# e_book_reader.net
KiCad netlist of a schematic drawn in EAGLE
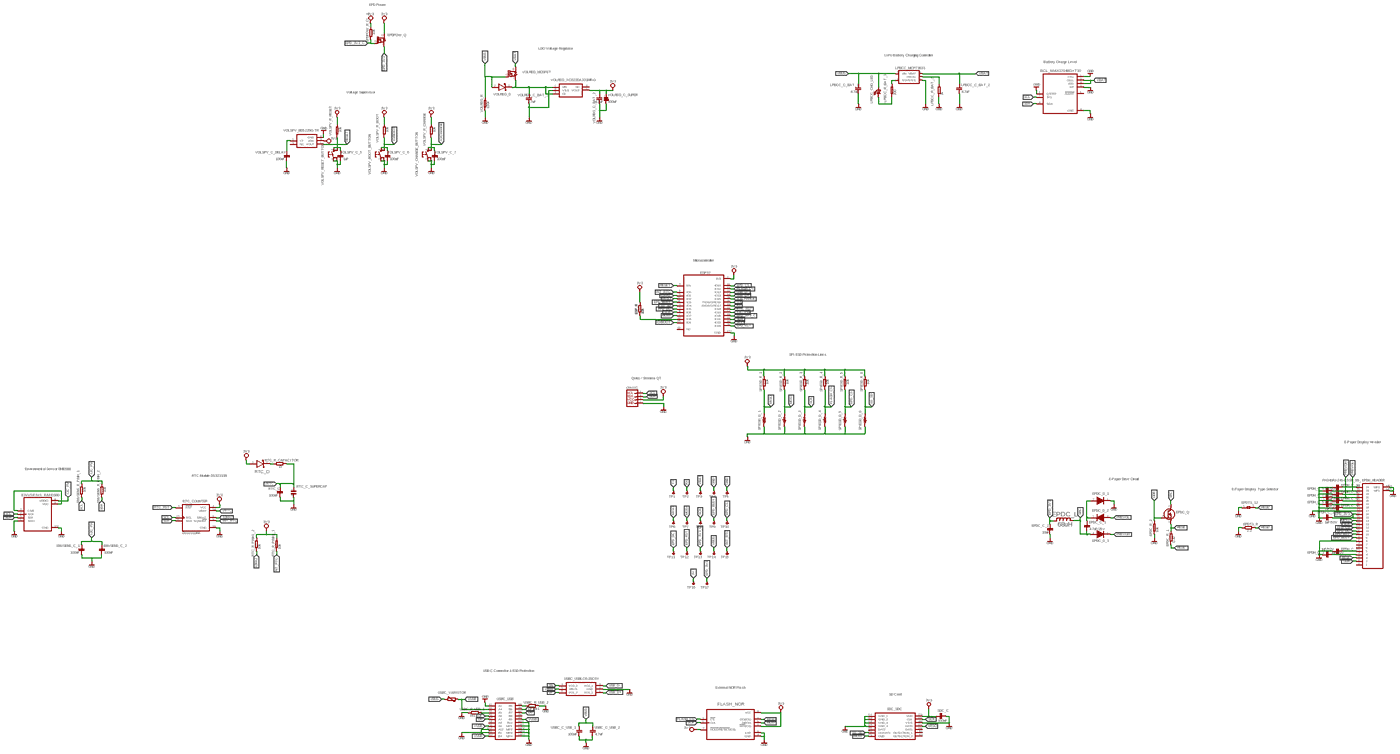
[diagram p0: schematic, sheet 1, overview]
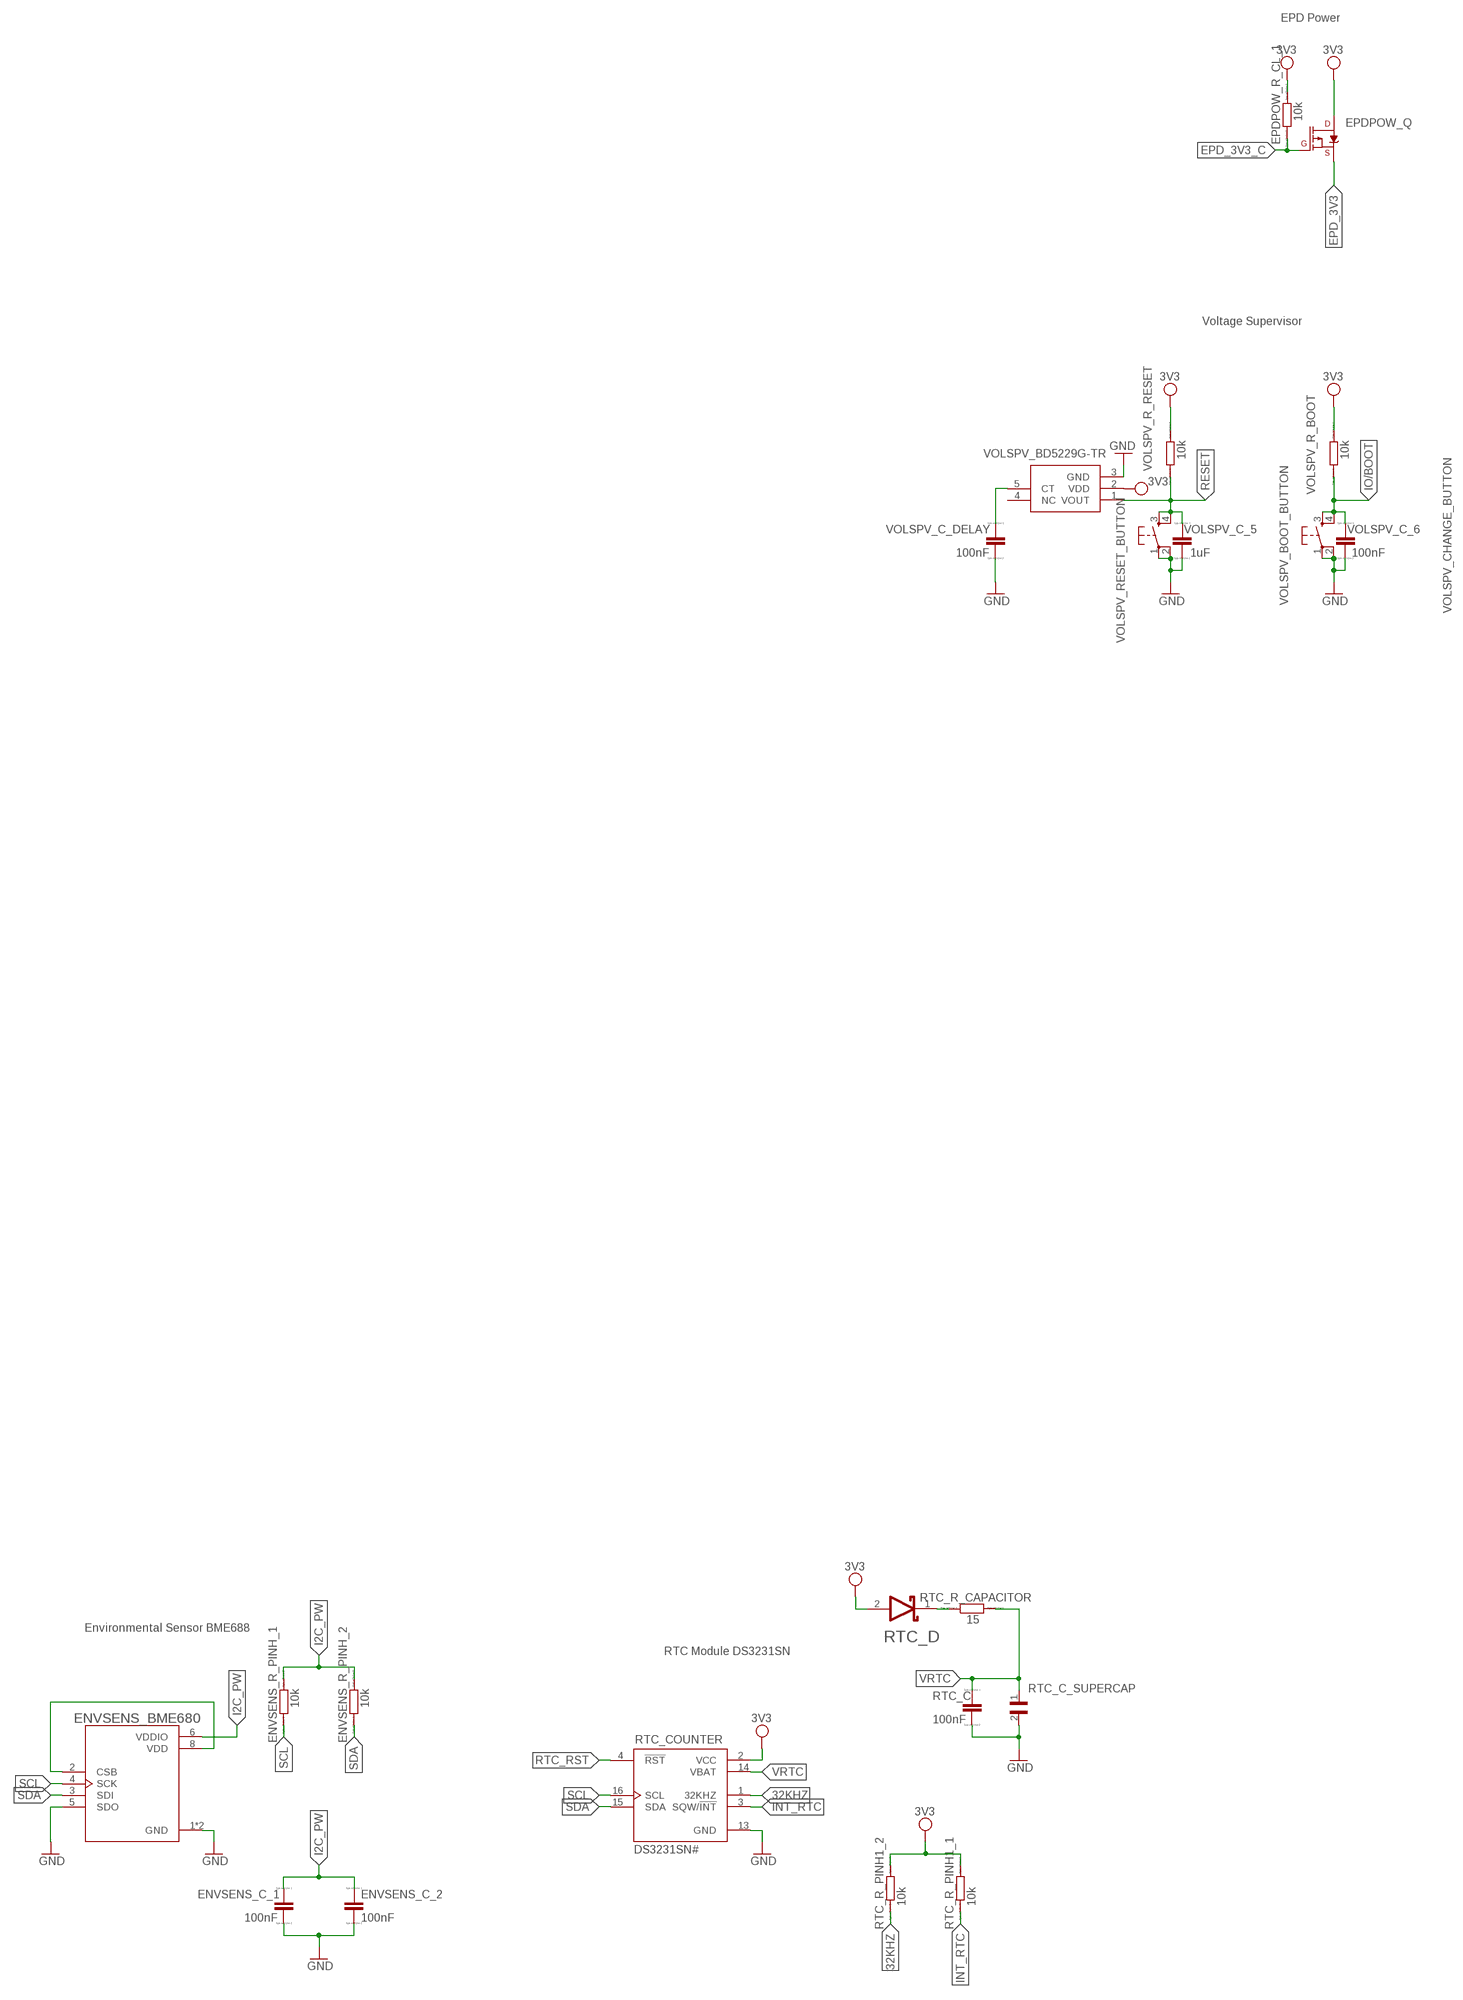
[diagram p1: schematic, sheet 1, part 1 of 5]
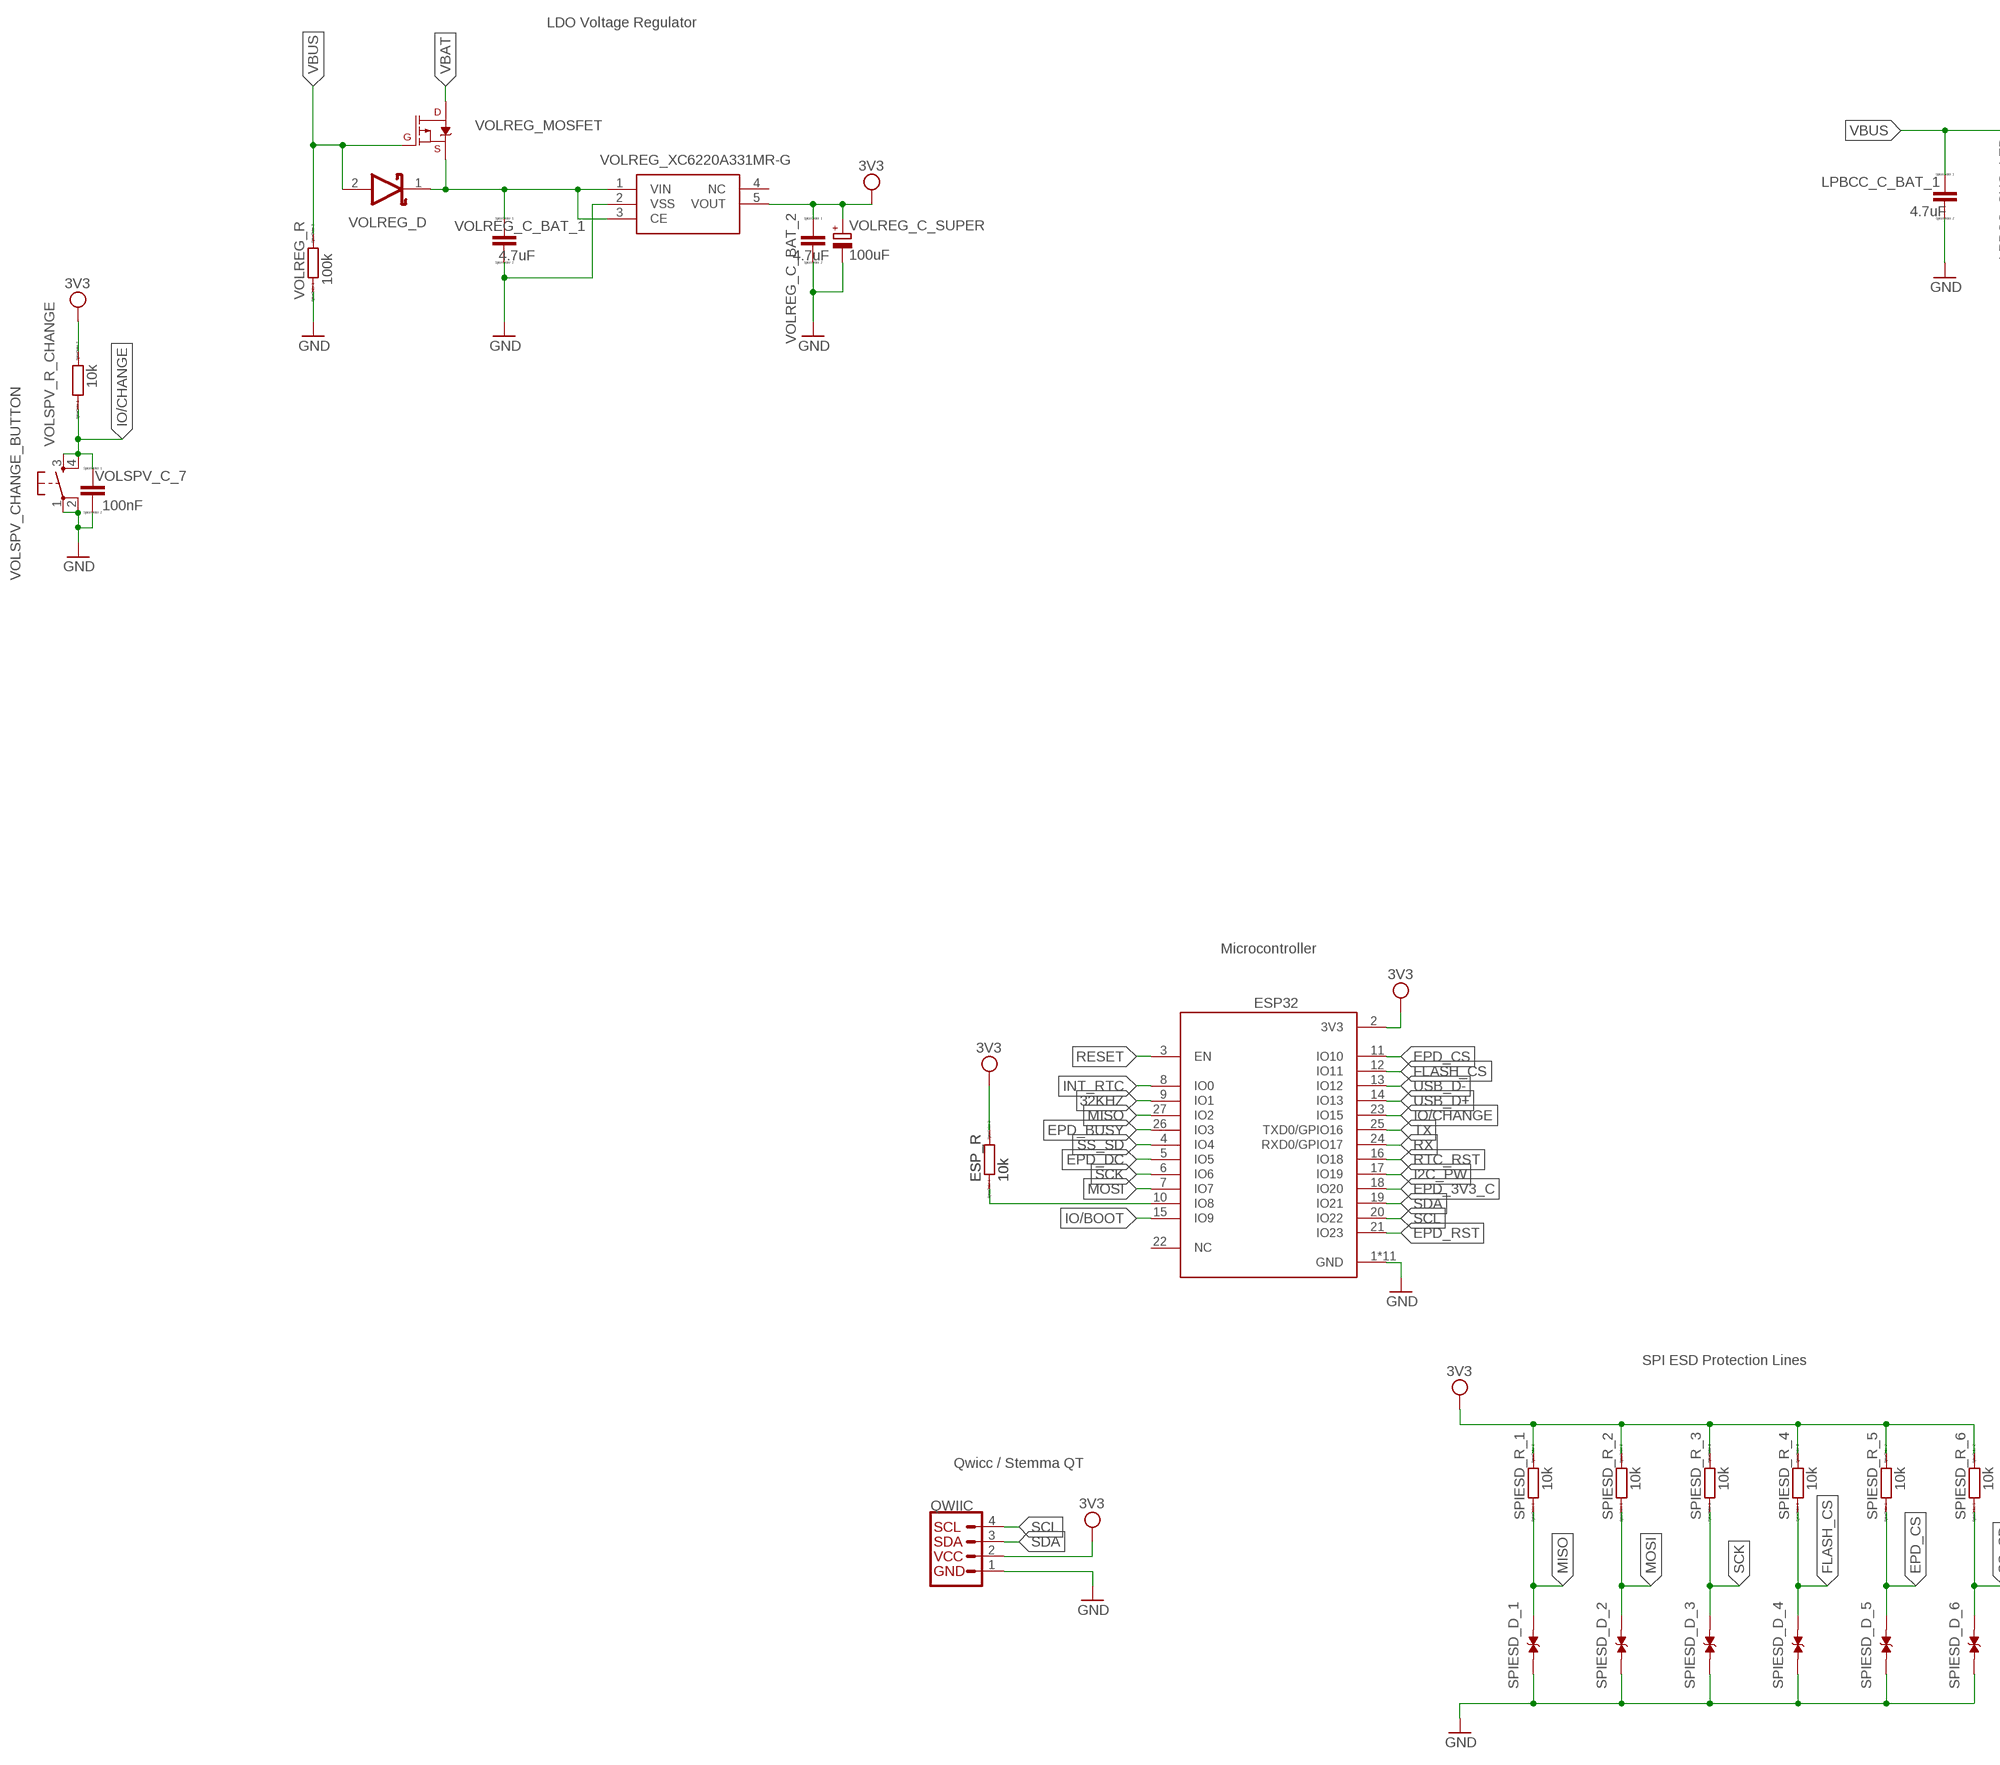
[diagram p2: schematic, sheet 1, part 2 of 5]
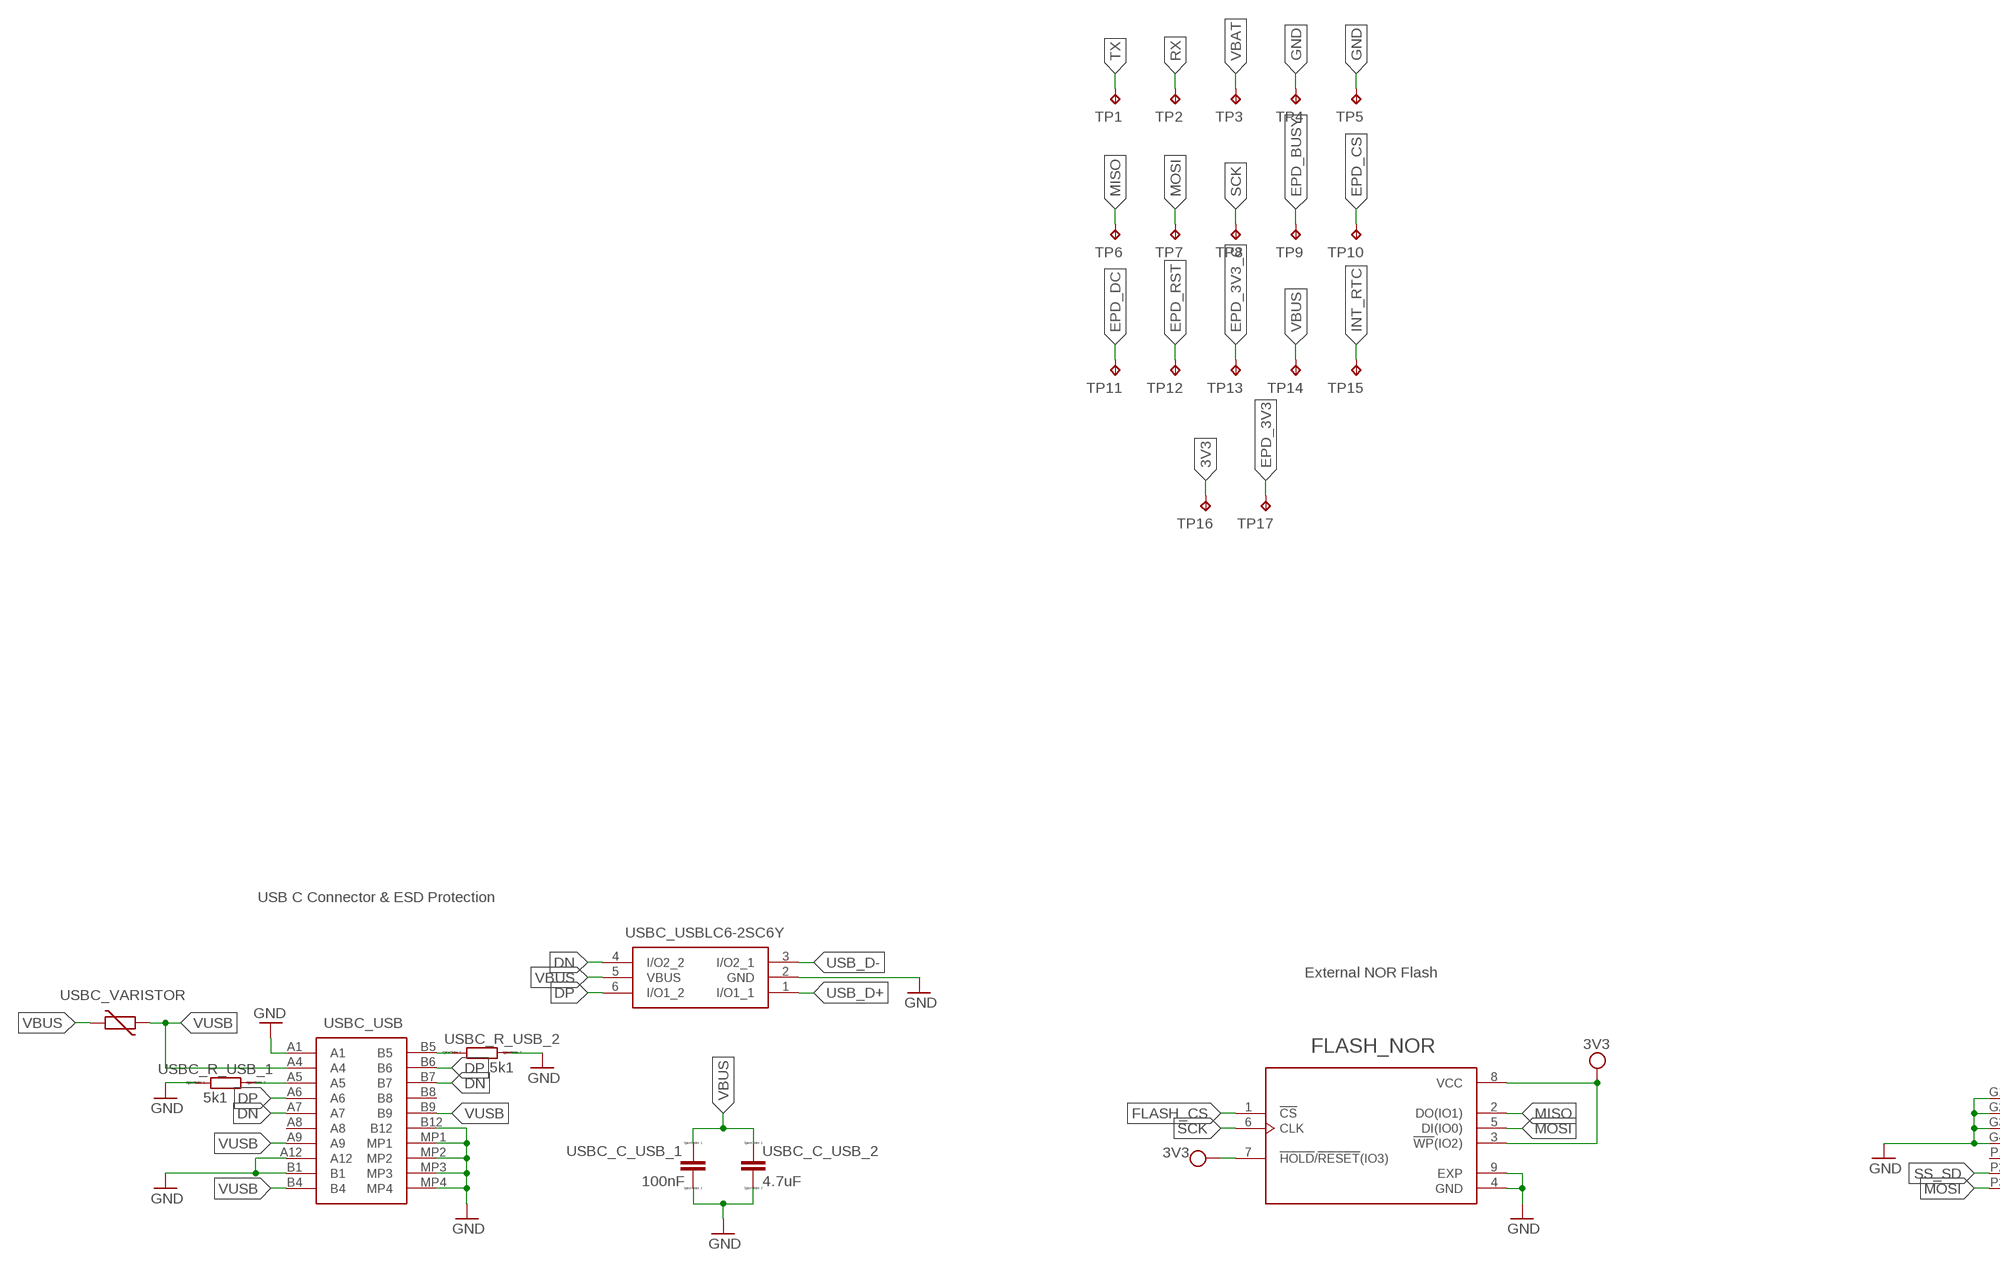
[diagram p3: schematic, sheet 1, part 3 of 5]
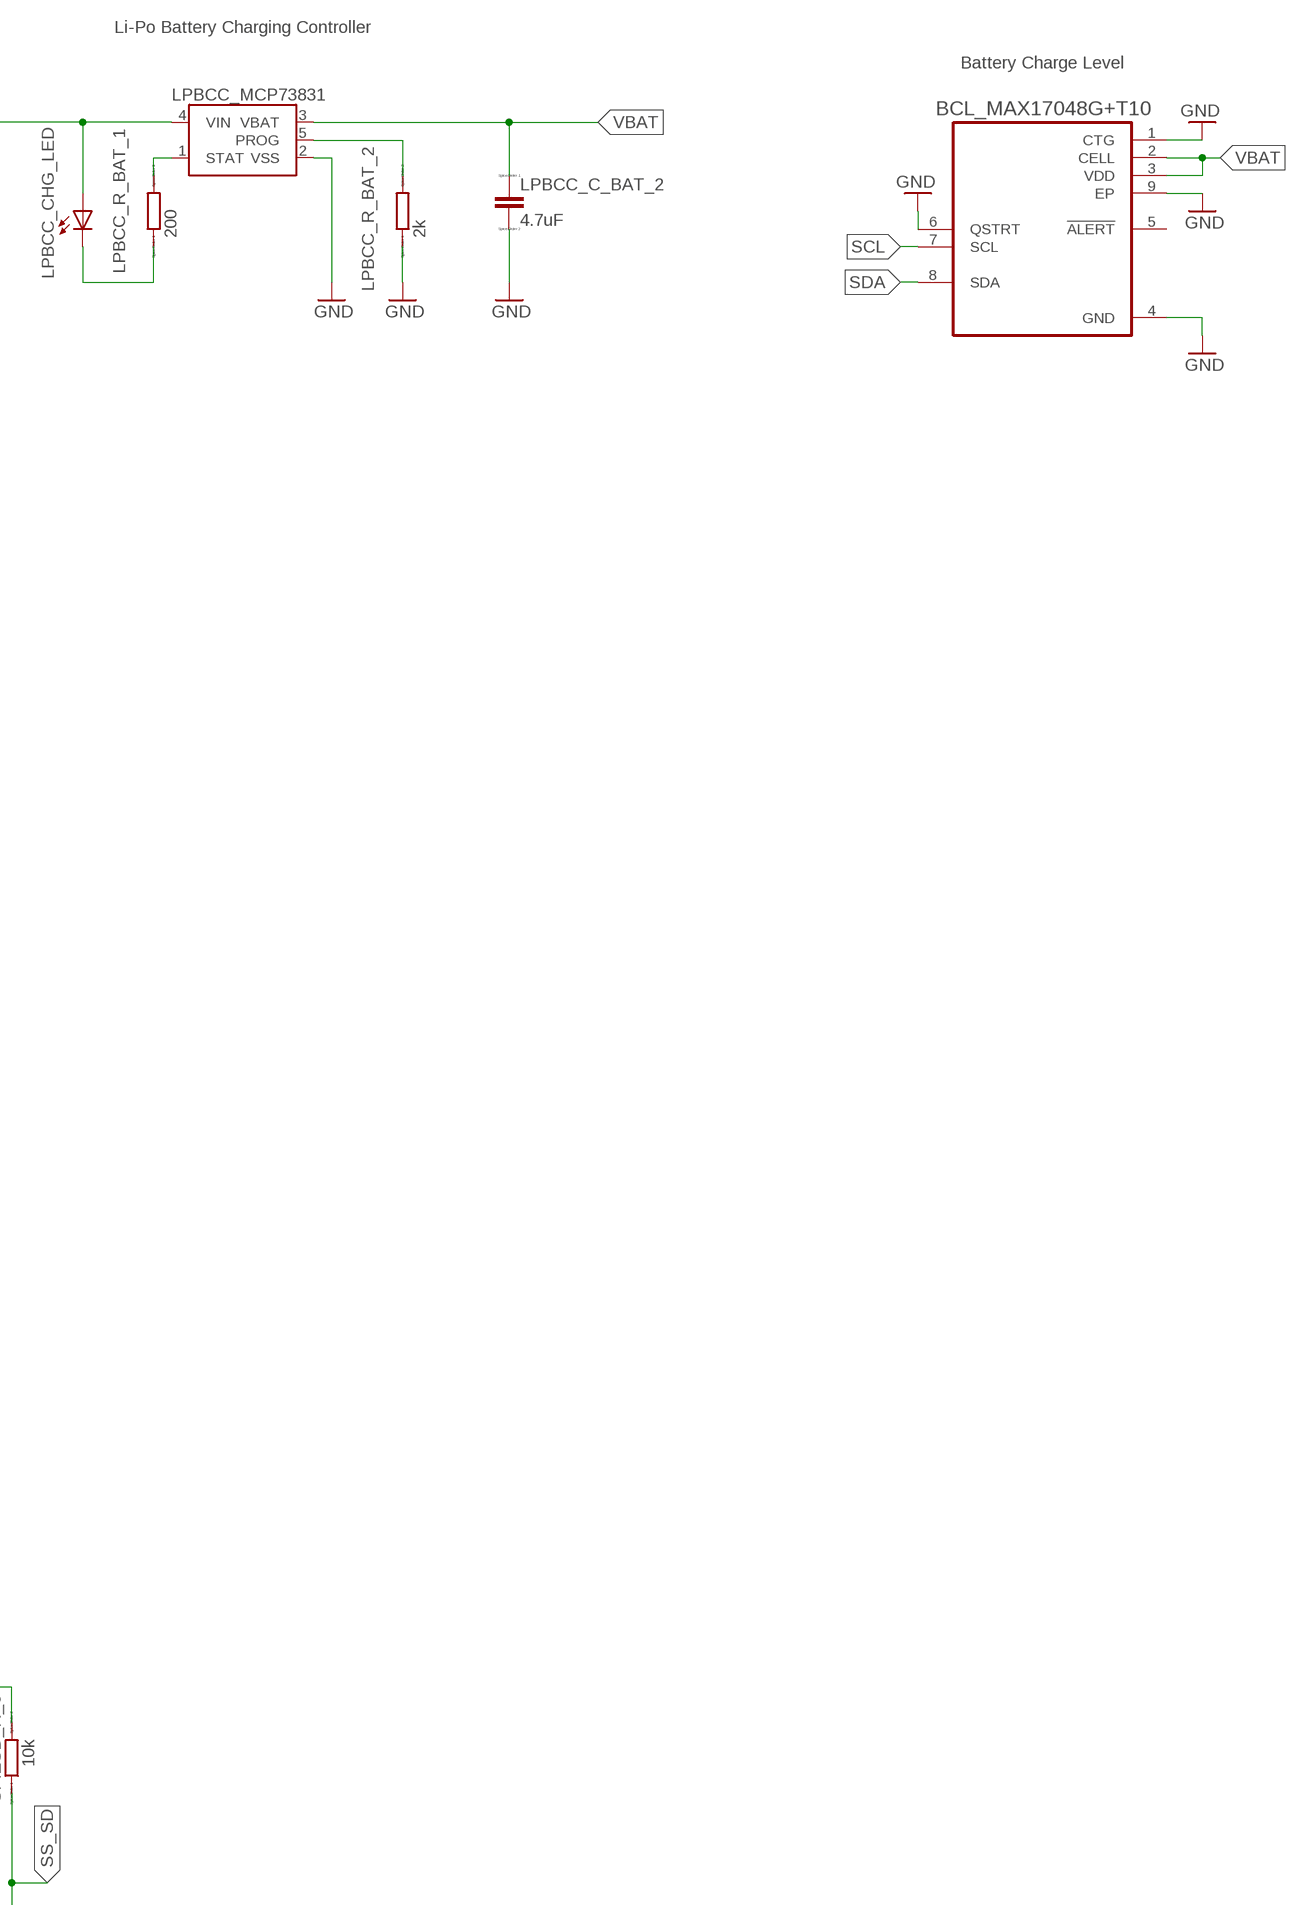
[diagram p4: schematic, sheet 1, part 4 of 5]
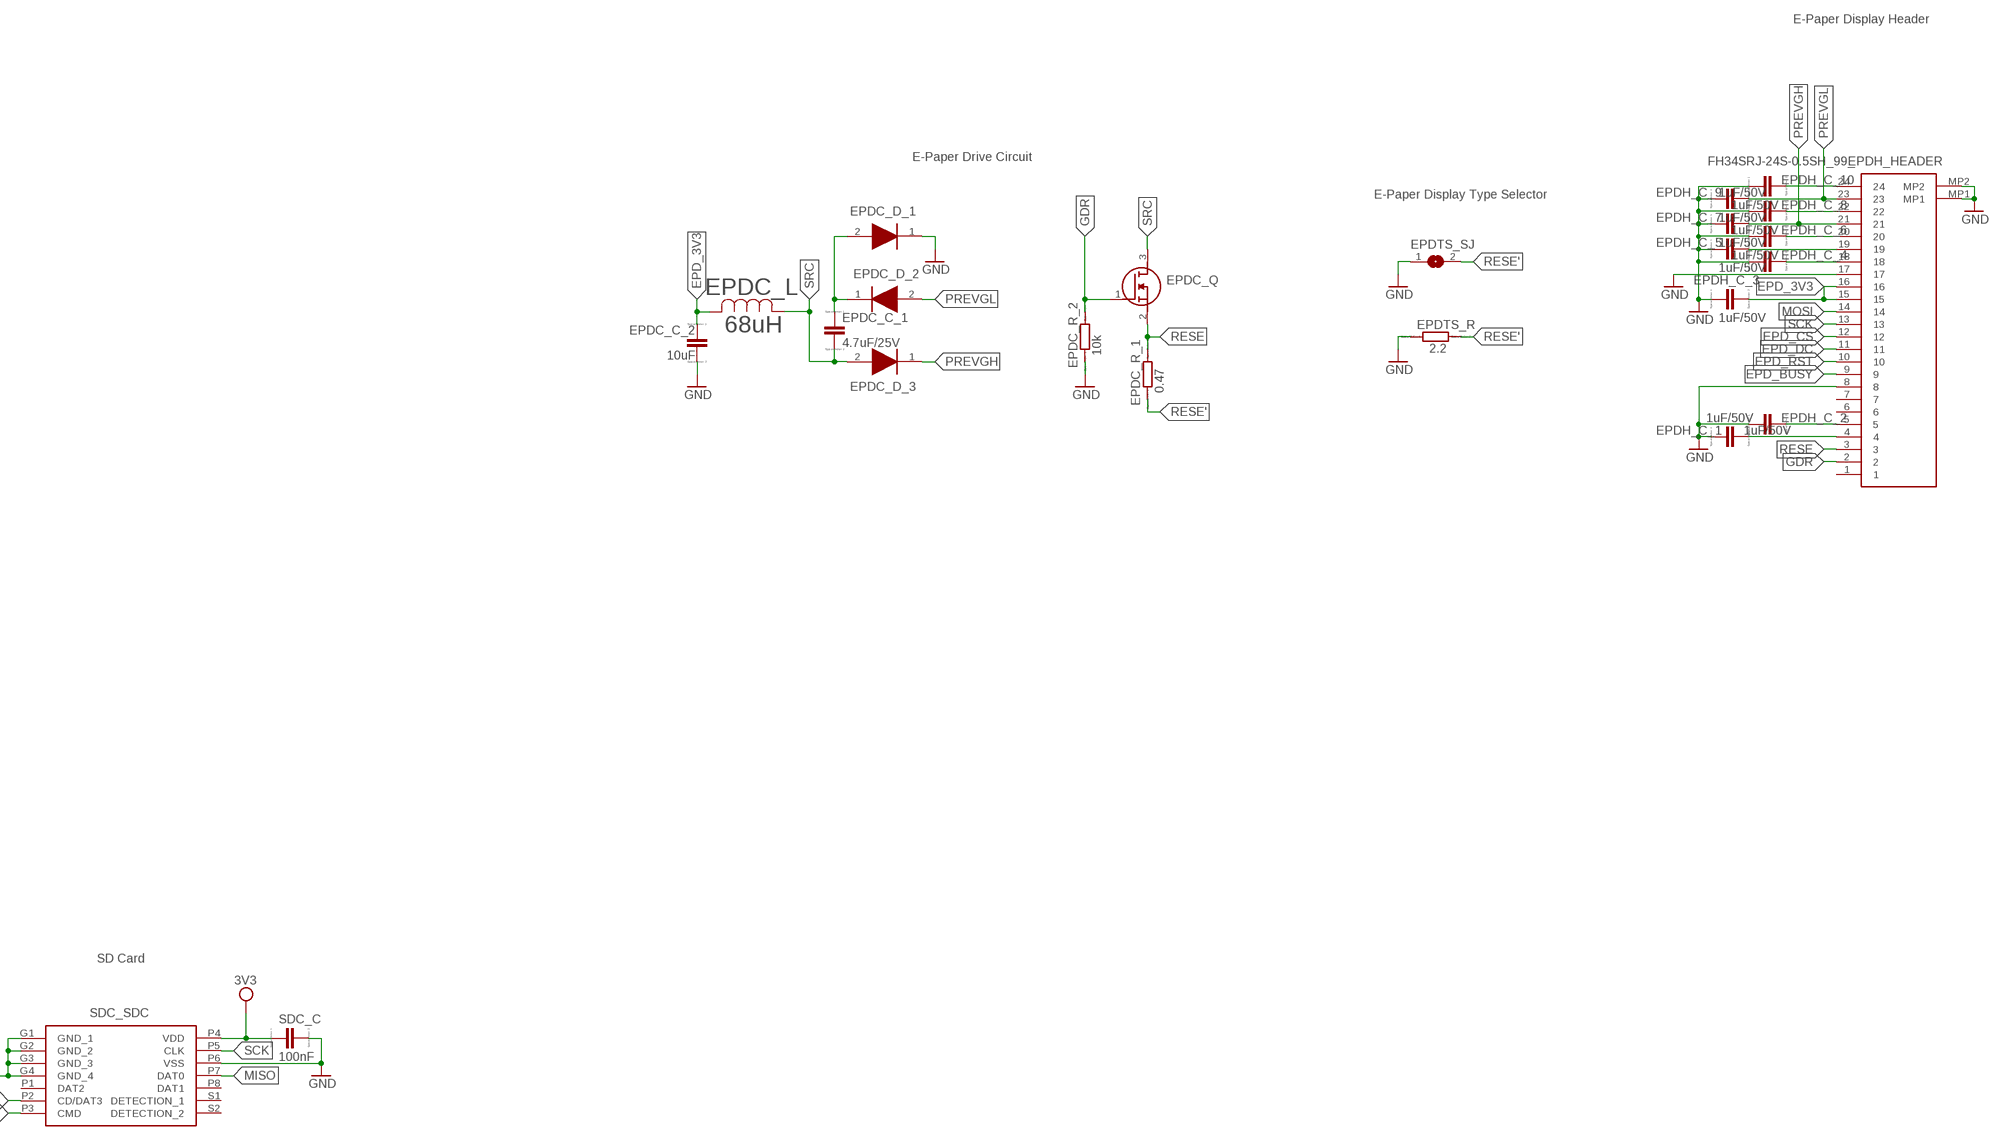
[diagram p5: schematic, sheet 1, part 5 of 5]

(export (version "E")
  (design (tool "Eeschema 10.0.6"))
  (components
    (comp (ref "BCL_MAX17048G+T10")
      (value "MAX17048G+T10")
      (footprint "eagle-import:SON50P200X200X80-9N")
      (libsource (lib "eagle-import") (part "MAX17048G+T10"))
    )
    (comp (ref "ENVSENS_BME680")
      (value "ESP32_WROVER_BME680_BME680")
      (footprint "eagle-import:ESP32_WROVER_BME680_PSON80P300X300X100-8N")
      (libsource (lib "eagle-import") (part "ESP32_WROVER_BME680_BME680"))
    )
    (comp (ref "ENVSENS_C_1")
      (value "100nF")
      (footprint "eagle-import:EAGLE-LTSPICE_C0402")
      (libsource (lib "eagle-import") (part "EAGLE-LTSPICE_CC0402"))
    )
    (comp (ref "ENVSENS_C_2")
      (value "100nF")
      (footprint "eagle-import:EAGLE-LTSPICE_C0402")
      (libsource (lib "eagle-import") (part "EAGLE-LTSPICE_CC0402"))
    )
    (comp (ref "ENVSENS_R_PINH_1")
      (value "10k")
      (footprint "eagle-import:ESP32_WROVER_EAGLE-LTSPICE_R0402")
      (libsource (lib "eagle-import") (part "ESP32_WROVER_EAGLE-LTSPICE_RR0402"))
    )
    (comp (ref "ENVSENS_R_PINH_2")
      (value "10k")
      (footprint "eagle-import:ESP32_WROVER_EAGLE-LTSPICE_R0402")
      (libsource (lib "eagle-import") (part "ESP32_WROVER_EAGLE-LTSPICE_RR0402"))
    )
    (comp (ref "EPDC_C_1")
      (value "4.7uF/25V")
      (footprint "eagle-import:EAGLE-LTSPICE_C0402")
      (libsource (lib "eagle-import") (part "EAGLE-LTSPICE_CC0402"))
    )
    (comp (ref "EPDC_C_2")
      (value "10uF")
      (footprint "eagle-import:EAGLE-LTSPICE_C0402")
      (libsource (lib "eagle-import") (part "EAGLE-LTSPICE_CC0402"))
    )
    (comp (ref "EPDC_D_1")
      (value "MBR0530")
      (footprint "eagle-import:SOD3716X135N")
      (libsource (lib "eagle-import") (part "MBR0530"))
    )
    (comp (ref "EPDC_D_2")
      (value "MBR0530")
      (footprint "eagle-import:SOD3716X135N")
      (libsource (lib "eagle-import") (part "MBR0530"))
    )
    (comp (ref "EPDC_D_3")
      (value "MBR0530")
      (footprint "eagle-import:SOD3716X135N")
      (libsource (lib "eagle-import") (part "MBR0530"))
    )
    (comp (ref "EPDC_L")
      (value "68uH")
      (footprint "eagle-import:IND_4828-WE-TPC_WRE")
      (libsource (lib "eagle-import") (part "744043680IND_4828-WE-TPC_WRE"))
    )
    (comp (ref "EPDC_Q")
      (value "SI1308EDL-T1-GE3")
      (footprint "eagle-import:SOT65P210X110-3N")
      (libsource (lib "eagle-import") (part "SI1308EDL-T1-GE3"))
    )
    (comp (ref "EPDC_R_1")
      (value "0.47")
      (footprint "eagle-import:ESP32_WROVER_EAGLE-LTSPICE_R0402")
      (libsource (lib "eagle-import") (part "ESP32_WROVER_EAGLE-LTSPICE_RR0402"))
    )
    (comp (ref "EPDC_R_2")
      (value "10k")
      (footprint "eagle-import:ESP32_WROVER_EAGLE-LTSPICE_R0402")
      (libsource (lib "eagle-import") (part "ESP32_WROVER_EAGLE-LTSPICE_RR0402"))
    )
    (comp (ref "EPDH_C_1")
      (value "1uF/50V")
      (footprint "eagle-import:EAGLE-LTSPICE_C0402")
      (libsource (lib "eagle-import") (part "EAGLE-LTSPICE_CC0402"))
    )
    (comp (ref "EPDH_C_2")
      (value "1uF/50V")
      (footprint "eagle-import:EAGLE-LTSPICE_C0402")
      (libsource (lib "eagle-import") (part "EAGLE-LTSPICE_CC0402"))
    )
    (comp (ref "EPDH_C_3")
      (value "1uF/50V")
      (footprint "eagle-import:EAGLE-LTSPICE_C0402")
      (libsource (lib "eagle-import") (part "EAGLE-LTSPICE_CC0402"))
    )
    (comp (ref "EPDH_C_4")
      (value "1uF/50V")
      (footprint "eagle-import:EAGLE-LTSPICE_C0402")
      (libsource (lib "eagle-import") (part "EAGLE-LTSPICE_CC0402"))
    )
    (comp (ref "EPDH_C_5")
      (value "1uF/50V")
      (footprint "eagle-import:EAGLE-LTSPICE_C0402")
      (libsource (lib "eagle-import") (part "EAGLE-LTSPICE_CC0402"))
    )
    (comp (ref "EPDH_C_6")
      (value "1uF/50V")
      (footprint "eagle-import:EAGLE-LTSPICE_C0402")
      (libsource (lib "eagle-import") (part "EAGLE-LTSPICE_CC0402"))
    )
    (comp (ref "EPDH_C_7")
      (value "1uF/50V")
      (footprint "eagle-import:EAGLE-LTSPICE_C0402")
      (libsource (lib "eagle-import") (part "EAGLE-LTSPICE_CC0402"))
    )
    (comp (ref "EPDH_C_8")
      (value "1uF/50V")
      (footprint "eagle-import:EAGLE-LTSPICE_C0402")
      (libsource (lib "eagle-import") (part "EAGLE-LTSPICE_CC0402"))
    )
    (comp (ref "EPDH_C_9")
      (value "1uF/50V")
      (footprint "eagle-import:EAGLE-LTSPICE_C0402")
      (libsource (lib "eagle-import") (part "EAGLE-LTSPICE_CC0402"))
    )
    (comp (ref "EPDH_C_10")
      (value "1uF/50V")
      (footprint "eagle-import:EAGLE-LTSPICE_C0402")
      (libsource (lib "eagle-import") (part "EAGLE-LTSPICE_CC0402"))
    )
    (comp (ref "EPDH_HEADER")
      (value "FH34SRJ-24S-0.5SH_99_")
      (footprint "eagle-import:FH34SRJ24S05SH99")
      (libsource (lib "eagle-import") (part "FH34SRJ-24S-0.5SH_99_"))
    )
    (comp (ref "EPDPOW_Q")
      (value "20V/4.2A/52mΩ/1.4W")
      (footprint "eagle-import:ESP32_WROVER_SPARKFUN-DISCRETESEMI_SOT23-3")
      (libsource (lib "eagle-import") (part "ESP32_WROVER_SPARKFUN-DISCRETESEMI_MOSFET_PCH-DMG2305UX-7"))
    )
    (comp (ref "EPDPOW_R_CL_1")
      (value "10k")
      (footprint "eagle-import:ESP32_WROVER_EAGLE-LTSPICE_R0402")
      (libsource (lib "eagle-import") (part "ESP32_WROVER_EAGLE-LTSPICE_RR0402"))
    )
    (comp (ref "EPDTS_R")
      (value "2.2")
      (footprint "eagle-import:ESP32_WROVER_EAGLE-LTSPICE_R0402")
      (libsource (lib "eagle-import") (part "ESP32_WROVER_EAGLE-LTSPICE_RR0402"))
    )
    (comp (ref "EPDTS_SJ")
      (value "SJ")
      (footprint "eagle-import:SJ")
      (libsource (lib "eagle-import") (part "SJ"))
    )
    (comp (ref "ESP32")
      (value "ESP32-C6-WROOM-1-N8")
      (footprint "eagle-import:XCVR_ESP32-C6-WROOM-1-N8")
      (fields (field (name "MF") "Espressif Systems"))
      (libsource (lib "eagle-import") (part "ESP32-C6-WROOM-1-N8"))
    )
    (comp (ref "ESP_R")
      (value "10k")
      (footprint "eagle-import:ESP32_WROVER_EAGLE-LTSPICE_R0402")
      (libsource (lib "eagle-import") (part "ESP32_WROVER_EAGLE-LTSPICE_RR0402"))
    )
    (comp (ref "FLASH_NOR")
      (value "W25Q512JVEIQ")
      (footprint "eagle-import:SON127P600X800X80-9N")
      (libsource (lib "eagle-import") (part "W25Q512JVEIQ"))
    )
    (comp (ref "LPBCC_CHG_LED")
      (value "ADAFRUIT_LED")
      (footprint "eagle-import:ADAFRUIT_CHIP-LED0603")
      (libsource (lib "eagle-import") (part "ADAFRUIT_LED"))
    )
    (comp (ref "LPBCC_C_BAT_1")
      (value "4.7uF")
      (footprint "eagle-import:EAGLE-LTSPICE_C0402")
      (libsource (lib "eagle-import") (part "EAGLE-LTSPICE_CC0402"))
    )
    (comp (ref "LPBCC_C_BAT_2")
      (value "4.7uF")
      (footprint "eagle-import:EAGLE-LTSPICE_C0402")
      (libsource (lib "eagle-import") (part "EAGLE-LTSPICE_CC0402"))
    )
    (comp (ref "LPBCC_MCP73831")
      (value "ESP32_WROVER_SPARKFUN-IC-POWER_MCP73831")
      (footprint "eagle-import:ESP32_WROVER_SPARKFUN-IC-POWER_SOT23-5")
      (libsource (lib "eagle-import") (part "ESP32_WROVER_SPARKFUN-IC-POWER_MCP73831"))
    )
    (comp (ref "LPBCC_R_BAT_1")
      (value "200")
      (footprint "eagle-import:ESP32_WROVER_EAGLE-LTSPICE_R0402")
      (libsource (lib "eagle-import") (part "ESP32_WROVER_EAGLE-LTSPICE_RR0402"))
    )
    (comp (ref "LPBCC_R_BAT_2")
      (value "2k")
      (footprint "eagle-import:ESP32_WROVER_EAGLE-LTSPICE_R0402")
      (libsource (lib "eagle-import") (part "ESP32_WROVER_EAGLE-LTSPICE_RR0402"))
    )
    (comp (ref "QWIIC")
      (value "QWIIC_RIGHT_ANGLE")
      (footprint "eagle-import:JST04_1MM_RA")
      (libsource (lib "eagle-import") (part "QWIIC_CONNECTORJS-1MM"))
    )
    (comp (ref "RTC_C")
      (value "100nF")
      (footprint "eagle-import:EAGLE-LTSPICE_C0402")
      (libsource (lib "eagle-import") (part "EAGLE-LTSPICE_CC0402"))
    )
    (comp (ref "RTC_COUNTER")
      (value "DS3231SN#")
      (footprint "eagle-import:SOIC127P1032X265-16N")
      (libsource (lib "eagle-import") (part "DS3231SN#"))
    )
    (comp (ref "RTC_C_SUPERCAP")
      (value "CPH3225A")
      (footprint "eagle-import:CAPCP3225X100N")
      (libsource (lib "eagle-import") (part "CPH3225A"))
    )
    (comp (ref "RTC_D")
      (value "ESP32_WROVER_AVX---SD0805S020S1R0_AVX_SD0805S020S1R0_0_0AVX_SD0805S020S1R0_0_0")
      (footprint "eagle-import:ESP32_WROVER_AVX---SD0805S020S1R0_AVX_SD0805S020S1R0_0")
      (libsource (lib "eagle-import") (part "ESP32_WROVER_AVX---SD0805S020S1R0_AVX_SD0805S020S1R0_0_0AVX_SD0805S020S1R0_0_0"))
    )
    (comp (ref "RTC_R_CAPACITOR")
      (value "15")
      (footprint "eagle-import:ESP32_WROVER_EAGLE-LTSPICE_R0402")
      (libsource (lib "eagle-import") (part "ESP32_WROVER_EAGLE-LTSPICE_RR0402"))
    )
    (comp (ref "RTC_R_PINH1_1")
      (value "10k")
      (footprint "eagle-import:ESP32_WROVER_EAGLE-LTSPICE_R0402")
      (libsource (lib "eagle-import") (part "ESP32_WROVER_EAGLE-LTSPICE_RR0402"))
    )
    (comp (ref "RTC_R_PINH1_2")
      (value "10k")
      (footprint "eagle-import:ESP32_WROVER_EAGLE-LTSPICE_R0402")
      (libsource (lib "eagle-import") (part "ESP32_WROVER_EAGLE-LTSPICE_RR0402"))
    )
    (comp (ref "SDC_C")
      (value "100nF")
      (footprint "eagle-import:EAGLE-LTSPICE_C0402")
      (libsource (lib "eagle-import") (part "EAGLE-LTSPICE_CC0402"))
    )
    (comp (ref "SDC_SDC")
      (value "112A-TAAR-R03_ATTEND")
      (footprint "eagle-import:112ATAARR03ATTEND")
      (libsource (lib "eagle-import") (part "112A-TAAR-R03_ATTEND"))
    )
    (comp (ref "SPIESD_D_1")
      (value "PGB1010603MR")
      (footprint "eagle-import:DIOC1608X36N")
      (libsource (lib "eagle-import") (part "PGB1010603MR"))
    )
    (comp (ref "SPIESD_D_2")
      (value "PGB1010603MR")
      (footprint "eagle-import:DIOC1608X36N")
      (libsource (lib "eagle-import") (part "PGB1010603MR"))
    )
    (comp (ref "SPIESD_D_3")
      (value "PGB1010603MR")
      (footprint "eagle-import:DIOC1608X36N")
      (libsource (lib "eagle-import") (part "PGB1010603MR"))
    )
    (comp (ref "SPIESD_D_4")
      (value "PGB1010603MR")
      (footprint "eagle-import:DIOC1608X36N")
      (libsource (lib "eagle-import") (part "PGB1010603MR"))
    )
    (comp (ref "SPIESD_D_5")
      (value "PGB1010603MR")
      (footprint "eagle-import:DIOC1608X36N")
      (libsource (lib "eagle-import") (part "PGB1010603MR"))
    )
    (comp (ref "SPIESD_D_6")
      (value "PGB1010603MR")
      (footprint "eagle-import:DIOC1608X36N")
      (libsource (lib "eagle-import") (part "PGB1010603MR"))
    )
    (comp (ref "SPIESD_R_1")
      (value "10k")
      (footprint "eagle-import:ESP32_WROVER_EAGLE-LTSPICE_R0402")
      (libsource (lib "eagle-import") (part "ESP32_WROVER_EAGLE-LTSPICE_RR0402"))
    )
    (comp (ref "SPIESD_R_2")
      (value "10k")
      (footprint "eagle-import:ESP32_WROVER_EAGLE-LTSPICE_R0402")
      (libsource (lib "eagle-import") (part "ESP32_WROVER_EAGLE-LTSPICE_RR0402"))
    )
    (comp (ref "SPIESD_R_3")
      (value "10k")
      (footprint "eagle-import:ESP32_WROVER_EAGLE-LTSPICE_R0402")
      (libsource (lib "eagle-import") (part "ESP32_WROVER_EAGLE-LTSPICE_RR0402"))
    )
    (comp (ref "SPIESD_R_4")
      (value "10k")
      (footprint "eagle-import:ESP32_WROVER_EAGLE-LTSPICE_R0402")
      (libsource (lib "eagle-import") (part "ESP32_WROVER_EAGLE-LTSPICE_RR0402"))
    )
    (comp (ref "SPIESD_R_5")
      (value "10k")
      (footprint "eagle-import:ESP32_WROVER_EAGLE-LTSPICE_R0402")
      (libsource (lib "eagle-import") (part "ESP32_WROVER_EAGLE-LTSPICE_RR0402"))
    )
    (comp (ref "SPIESD_R_6")
      (value "10k")
      (footprint "eagle-import:ESP32_WROVER_EAGLE-LTSPICE_R0402")
      (libsource (lib "eagle-import") (part "ESP32_WROVER_EAGLE-LTSPICE_RR0402"))
    )
    (comp (ref "TP1")
      (value "TPTP20R")
      (footprint "eagle-import:TP20R")
      (libsource (lib "eagle-import") (part "TPTP20R"))
    )
    (comp (ref "TP2")
      (value "TPTP20R")
      (footprint "eagle-import:TP20R")
      (libsource (lib "eagle-import") (part "TPTP20R"))
    )
    (comp (ref "TP3")
      (value "TPTP20R")
      (footprint "eagle-import:TP20R")
      (libsource (lib "eagle-import") (part "TPTP20R"))
    )
    (comp (ref "TP4")
      (value "TPTP20R")
      (footprint "eagle-import:TP20R")
      (libsource (lib "eagle-import") (part "TPTP20R"))
    )
    (comp (ref "TP5")
      (value "TPTP20R")
      (footprint "eagle-import:TP20R")
      (libsource (lib "eagle-import") (part "TPTP20R"))
    )
    (comp (ref "TP6")
      (value "TPTP20R")
      (footprint "eagle-import:TP20R")
      (libsource (lib "eagle-import") (part "TPTP20R"))
    )
    (comp (ref "TP7")
      (value "TPTP20R")
      (footprint "eagle-import:TP20R")
      (libsource (lib "eagle-import") (part "TPTP20R"))
    )
    (comp (ref "TP8")
      (value "TPTP20R")
      (footprint "eagle-import:TP20R")
      (libsource (lib "eagle-import") (part "TPTP20R"))
    )
    (comp (ref "TP9")
      (value "TPTP20R")
      (footprint "eagle-import:TP20R")
      (libsource (lib "eagle-import") (part "TPTP20R"))
    )
    (comp (ref "TP10")
      (value "TPTP20R")
      (footprint "eagle-import:TP20R")
      (libsource (lib "eagle-import") (part "TPTP20R"))
    )
    (comp (ref "TP11")
      (value "TPTP20R")
      (footprint "eagle-import:TP20R")
      (libsource (lib "eagle-import") (part "TPTP20R"))
    )
    (comp (ref "TP12")
      (value "TPTP20R")
      (footprint "eagle-import:TP20R")
      (libsource (lib "eagle-import") (part "TPTP20R"))
    )
    (comp (ref "TP13")
      (value "TPTP20R")
      (footprint "eagle-import:TP20R")
      (libsource (lib "eagle-import") (part "TPTP20R"))
    )
    (comp (ref "TP14")
      (value "TPTP20R")
      (footprint "eagle-import:TP20R")
      (libsource (lib "eagle-import") (part "TPTP20R"))
    )
    (comp (ref "TP15")
      (value "TPTP20R")
      (footprint "eagle-import:TP20R")
      (libsource (lib "eagle-import") (part "TPTP20R"))
    )
    (comp (ref "TP16")
      (value "TPTP20R")
      (footprint "eagle-import:TP20R")
      (libsource (lib "eagle-import") (part "TPTP20R"))
    )
    (comp (ref "TP17")
      (value "TPTP20R")
      (footprint "eagle-import:TP20R")
      (libsource (lib "eagle-import") (part "TPTP20R"))
    )
    (comp (ref "USBC_C_USB_1")
      (value "100nF")
      (footprint "eagle-import:EAGLE-LTSPICE_C0402")
      (libsource (lib "eagle-import") (part "EAGLE-LTSPICE_CC0402"))
    )
    (comp (ref "USBC_C_USB_2")
      (value "4.7uF")
      (footprint "eagle-import:EAGLE-LTSPICE_C0402")
      (libsource (lib "eagle-import") (part "EAGLE-LTSPICE_CC0402"))
    )
    (comp (ref "USBC_R_USB_1")
      (value "5k1")
      (footprint "eagle-import:ESP32_WROVER_EAGLE-LTSPICE_R0402")
      (libsource (lib "eagle-import") (part "ESP32_WROVER_EAGLE-LTSPICE_RR0402"))
    )
    (comp (ref "USBC_R_USB_2")
      (value "5k1")
      (footprint "eagle-import:ESP32_WROVER_EAGLE-LTSPICE_R0402")
      (libsource (lib "eagle-import") (part "ESP32_WROVER_EAGLE-LTSPICE_RR0402"))
    )
    (comp (ref "USBC_USB")
      (value "SAMACSYS_PARTS_USB4110-GF-A")
      (footprint "eagle-import:SAMACSYS_PARTS_USB4110GFA")
      (libsource (lib "eagle-import") (part "SAMACSYS_PARTS_USB4110-GF-A"))
    )
    (comp (ref "USBC_USBLC6-2SC6Y")
      (value "USBLC6-2SC6Y")
      (footprint "eagle-import:SOT95P280X145-6N")
      (libsource (lib "eagle-import") (part "USBLC6-2SC6Y"))
    )
    (comp (ref "USBC_VARISTOR")
      (value "ESP32C6_VARISTORCN1812")
      (footprint "eagle-import:ESP32C6_VARISTOR_CT_CN1812")
      (libsource (lib "eagle-import") (part "ESP32C6_VARISTORCN1812"))
    )
    (comp (ref "VOLREG_C_BAT_1")
      (value "4.7uF")
      (footprint "eagle-import:EAGLE-LTSPICE_C0402")
      (libsource (lib "eagle-import") (part "EAGLE-LTSPICE_CC0402"))
    )
    (comp (ref "VOLREG_C_BAT_2")
      (value "4.7uF")
      (footprint "eagle-import:EAGLE-LTSPICE_C0402")
      (libsource (lib "eagle-import") (part "EAGLE-LTSPICE_CC0402"))
    )
    (comp (ref "VOLREG_C_SUPER")
      (value "100uF")
      (footprint "eagle-import:RCL_CT3528")
      (libsource (lib "eagle-import") (part "RCL_CPOL-EUCT3528"))
    )
    (comp (ref "VOLREG_D")
      (value "ESP32_WROVER_AVX---SD0805S020S1R0_AVX_SD0805S020S1R0_0_0AVX_SD0805S020S1R0_0_0")
      (footprint "eagle-import:ESP32_WROVER_AVX---SD0805S020S1R0_AVX_SD0805S020S1R0_0")
      (libsource (lib "eagle-import") (part "ESP32_WROVER_AVX---SD0805S020S1R0_AVX_SD0805S020S1R0_0_0AVX_SD0805S020S1R0_0_0"))
    )
    (comp (ref "VOLREG_MOSFET")
      (value "20V/4.2A/52mΩ/1.4W")
      (footprint "eagle-import:ESP32_WROVER_SPARKFUN-DISCRETESEMI_SOT23-3")
      (libsource (lib "eagle-import") (part "ESP32_WROVER_SPARKFUN-DISCRETESEMI_MOSFET_PCH-DMG2305UX-7"))
    )
    (comp (ref "VOLREG_R")
      (value "100k")
      (footprint "eagle-import:ESP32_WROVER_EAGLE-LTSPICE_R0402")
      (libsource (lib "eagle-import") (part "ESP32_WROVER_EAGLE-LTSPICE_RR0402"))
    )
    (comp (ref "VOLREG_XC6220A331MR-G")
      (value "XC6220A331MR-G")
      (footprint "eagle-import:SOT95P280X125-5N")
      (libsource (lib "eagle-import") (part "XC6220A331MR-G"))
    )
    (comp (ref "VOLSPV_BD5229G-TR")
      (value "BD5229G-TR")
      (footprint "eagle-import:SOT95P280X125-5N")
      (libsource (lib "eagle-import") (part "BD5229G-TR"))
    )
    (comp (ref "VOLSPV_BOOT_BUTTON")
      (value "BUTTON_CUSYOMV1")
      (footprint "eagle-import:MYBUTTON")
      (libsource (lib "eagle-import") (part "BUTTON_CUSYOMV1"))
    )
    (comp (ref "VOLSPV_CHANGE_BUTTON")
      (value "BUTTON_CUSYOMV1")
      (footprint "eagle-import:MYBUTTON")
      (libsource (lib "eagle-import") (part "BUTTON_CUSYOMV1"))
    )
    (comp (ref "VOLSPV_C_5")
      (value "1uF")
      (footprint "eagle-import:EAGLE-LTSPICE_C0402")
      (libsource (lib "eagle-import") (part "EAGLE-LTSPICE_CC0402"))
    )
    (comp (ref "VOLSPV_C_6")
      (value "100nF")
      (footprint "eagle-import:EAGLE-LTSPICE_C0402")
      (libsource (lib "eagle-import") (part "EAGLE-LTSPICE_CC0402"))
    )
    (comp (ref "VOLSPV_C_7")
      (value "100nF")
      (footprint "eagle-import:EAGLE-LTSPICE_C0402")
      (libsource (lib "eagle-import") (part "EAGLE-LTSPICE_CC0402"))
    )
    (comp (ref "VOLSPV_C_DELAY")
      (value "100nF")
      (footprint "eagle-import:EAGLE-LTSPICE_C0402")
      (libsource (lib "eagle-import") (part "EAGLE-LTSPICE_CC0402"))
    )
    (comp (ref "VOLSPV_RESET_BUTTON")
      (value "BUTTON_CUSYOMV1")
      (footprint "eagle-import:MYBUTTON")
      (libsource (lib "eagle-import") (part "BUTTON_CUSYOMV1"))
    )
    (comp (ref "VOLSPV_R_BOOT")
      (value "10k")
      (footprint "eagle-import:ESP32_WROVER_EAGLE-LTSPICE_R0402")
      (libsource (lib "eagle-import") (part "ESP32_WROVER_EAGLE-LTSPICE_RR0402"))
    )
    (comp (ref "VOLSPV_R_CHANGE")
      (value "10k")
      (footprint "eagle-import:ESP32_WROVER_EAGLE-LTSPICE_R0402")
      (libsource (lib "eagle-import") (part "ESP32_WROVER_EAGLE-LTSPICE_RR0402"))
    )
    (comp (ref "VOLSPV_R_RESET")
      (value "10k")
      (footprint "eagle-import:ESP32_WROVER_EAGLE-LTSPICE_R0402")
      (libsource (lib "eagle-import") (part "ESP32_WROVER_EAGLE-LTSPICE_RR0402"))
    )
  )
  (nets
    (net (code "1") (name "3V3") (class "Default")
      (node (ref "EPDPOW_Q") (pin "3") (pinfunction "D_3") (pintype "bidirectional"))
      (node (ref "EPDPOW_R_CL_1") (pin "2") (pinfunction "2_2") (pintype "passive"))
      (node (ref "ESP32") (pin "2") (pinfunction "3V3_2") (pintype "power_in"))
      (node (ref "ESP_R") (pin "2") (pinfunction "2_2") (pintype "passive"))
      (node (ref "FLASH_NOR") (pin "3") (pinfunction "~{WP}(IO2)_3") (pintype "bidirectional"))
      (node (ref "FLASH_NOR") (pin "7") (pinfunction "~{HOLD}/~{RESET}(IO3)_7") (pintype "bidirectional"))
      (node (ref "FLASH_NOR") (pin "8") (pinfunction "VCC_8") (pintype "power_in"))
      (node (ref "QWIIC") (pin "2") (pinfunction "2_2") (pintype "power_in"))
      (node (ref "RTC_COUNTER") (pin "2") (pinfunction "VCC_2") (pintype "power_in"))
      (node (ref "RTC_D") (pin "2") (pinfunction "ANODE_2") (pintype "bidirectional"))
      (node (ref "RTC_R_PINH1_1") (pin "2") (pinfunction "2_2") (pintype "passive"))
      (node (ref "RTC_R_PINH1_2") (pin "2") (pinfunction "2_2") (pintype "passive"))
      (node (ref "SDC_C") (pin "1") (pinfunction "1_1") (pintype "passive"))
      (node (ref "SDC_SDC") (pin "P4") (pinfunction "VDD_P4") (pintype "bidirectional"))
      (node (ref "SPIESD_R_1") (pin "2") (pinfunction "2_2") (pintype "passive"))
      (node (ref "SPIESD_R_2") (pin "2") (pinfunction "2_2") (pintype "passive"))
      (node (ref "SPIESD_R_3") (pin "2") (pinfunction "2_2") (pintype "passive"))
      (node (ref "SPIESD_R_4") (pin "2") (pinfunction "2_2") (pintype "passive"))
      (node (ref "SPIESD_R_5") (pin "2") (pinfunction "2_2") (pintype "passive"))
      (node (ref "SPIESD_R_6") (pin "2") (pinfunction "2_2") (pintype "passive"))
      (node (ref "TP16") (pin "TP") (pinfunction "TP_TP") (pintype "input"))
      (node (ref "VOLREG_C_BAT_2") (pin "1") (pinfunction "1_1") (pintype "passive"))
      (node (ref "VOLREG_C_SUPER") (pin "+") (pinfunction "+_+") (pintype "passive"))
      (node (ref "VOLREG_XC6220A331MR-G") (pin "5") (pinfunction "VOUT_5") (pintype "bidirectional"))
      (node (ref "VOLSPV_BD5229G-TR") (pin "2") (pinfunction "VDD_2") (pintype "bidirectional"))
      (node (ref "VOLSPV_R_BOOT") (pin "2") (pinfunction "2_2") (pintype "passive"))
      (node (ref "VOLSPV_R_CHANGE") (pin "2") (pinfunction "2_2") (pintype "passive"))
      (node (ref "VOLSPV_R_RESET") (pin "2") (pinfunction "2_2") (pintype "passive"))
    )
    (net (code "2") (name "32KHZ") (class "Default")
      (node (ref "ESP32") (pin "9") (pinfunction "IO1_9") (pintype "bidirectional"))
      (node (ref "RTC_COUNTER") (pin "1") (pinfunction "32KHZ_1") (pintype "output"))
      (node (ref "RTC_R_PINH1_2") (pin "1") (pinfunction "1_1") (pintype "passive"))
    )
    (net (code "3") (name "DN") (class "Default")
      (node (ref "USBC_USB") (pin "A7") (pinfunction "A7_A7") (pintype "bidirectional"))
      (node (ref "USBC_USB") (pin "B7") (pinfunction "B7_B7") (pintype "bidirectional"))
      (node (ref "USBC_USBLC6-2SC6Y") (pin "4") (pinfunction "I/O2_2_4") (pintype "bidirectional"))
    )
    (net (code "4") (name "DP") (class "Default")
      (node (ref "USBC_USB") (pin "A6") (pinfunction "A6_A6") (pintype "bidirectional"))
      (node (ref "USBC_USB") (pin "B6") (pinfunction "B6_B6") (pintype "bidirectional"))
      (node (ref "USBC_USBLC6-2SC6Y") (pin "6") (pinfunction "I/O1_2_6") (pintype "bidirectional"))
    )
    (net (code "5") (name "EPD_3V3") (class "Default")
      (node (ref "EPDC_C_2") (pin "1") (pinfunction "1_1") (pintype "passive"))
      (node (ref "EPDC_L") (pin "2") (pinfunction "2_2") (pintype "passive"))
      (node (ref "EPDH_C_3") (pin "2") (pinfunction "2_2") (pintype "passive"))
      (node (ref "EPDH_HEADER") (pin "15") (pinfunction "15_15") (pintype "bidirectional"))
      (node (ref "EPDH_HEADER") (pin "16") (pinfunction "16_16") (pintype "bidirectional"))
      (node (ref "EPDPOW_Q") (pin "2") (pinfunction "S_2") (pintype "bidirectional"))
      (node (ref "TP17") (pin "TP") (pinfunction "TP_TP") (pintype "input"))
    )
    (net (code "6") (name "EPD_3V3_C") (class "Default")
      (node (ref "EPDPOW_Q") (pin "1") (pinfunction "G_1") (pintype "bidirectional"))
      (node (ref "EPDPOW_R_CL_1") (pin "1") (pinfunction "1_1") (pintype "passive"))
      (node (ref "ESP32") (pin "18") (pinfunction "IO20_18") (pintype "bidirectional"))
      (node (ref "TP13") (pin "TP") (pinfunction "TP_TP") (pintype "input"))
    )
    (net (code "7") (name "EPD_BUSY") (class "Default")
      (node (ref "EPDH_HEADER") (pin "9") (pinfunction "9_9") (pintype "bidirectional"))
      (node (ref "ESP32") (pin "26") (pinfunction "IO3_26") (pintype "bidirectional"))
      (node (ref "TP9") (pin "TP") (pinfunction "TP_TP") (pintype "input"))
    )
    (net (code "8") (name "EPD_CS") (class "Default")
      (node (ref "EPDH_HEADER") (pin "12") (pinfunction "12_12") (pintype "bidirectional"))
      (node (ref "ESP32") (pin "11") (pinfunction "IO10_11") (pintype "bidirectional"))
      (node (ref "SPIESD_D_5") (pin "2") (pinfunction "2_2") (pintype "passive"))
      (node (ref "SPIESD_R_5") (pin "1") (pinfunction "1_1") (pintype "passive"))
      (node (ref "TP10") (pin "TP") (pinfunction "TP_TP") (pintype "input"))
    )
    (net (code "9") (name "EPD_DC") (class "Default")
      (node (ref "EPDH_HEADER") (pin "11") (pinfunction "11_11") (pintype "bidirectional"))
      (node (ref "ESP32") (pin "5") (pinfunction "IO5_5") (pintype "bidirectional"))
      (node (ref "TP11") (pin "TP") (pinfunction "TP_TP") (pintype "input"))
    )
    (net (code "10") (name "EPD_RST") (class "Default")
      (node (ref "EPDH_HEADER") (pin "10") (pinfunction "10_10") (pintype "bidirectional"))
      (node (ref "ESP32") (pin "21") (pinfunction "IO23_21") (pintype "bidirectional"))
      (node (ref "TP12") (pin "TP") (pinfunction "TP_TP") (pintype "input"))
    )
    (net (code "11") (name "FLASH_CS") (class "Default")
      (node (ref "ESP32") (pin "12") (pinfunction "IO11_12") (pintype "bidirectional"))
      (node (ref "FLASH_NOR") (pin "1") (pinfunction "~{CS}_1") (pintype "input"))
      (node (ref "SPIESD_D_4") (pin "2") (pinfunction "2_2") (pintype "passive"))
      (node (ref "SPIESD_R_4") (pin "1") (pinfunction "1_1") (pintype "passive"))
    )
    (net (code "12") (name "GDR") (class "Default")
      (node (ref "EPDC_Q") (pin "1") (pinfunction "G_1") (pintype "bidirectional"))
      (node (ref "EPDC_R_2") (pin "2") (pinfunction "2_2") (pintype "passive"))
      (node (ref "EPDH_HEADER") (pin "2") (pinfunction "2_2") (pintype "bidirectional"))
    )
    (net (code "13") (name "GND") (class "Default")
      (node (ref "BCL_MAX17048G+T10") (pin "1") (pinfunction "CTG_1") (pintype "power_in"))
      (node (ref "BCL_MAX17048G+T10") (pin "4") (pinfunction "GND_4") (pintype "power_in"))
      (node (ref "BCL_MAX17048G+T10") (pin "6") (pinfunction "QSTRT_6") (pintype "input"))
      (node (ref "BCL_MAX17048G+T10") (pin "9") (pinfunction "EP_9") (pintype "power_in"))
      (node (ref "ENVSENS_BME680") (pin "1") (pinfunction "GND_1") (pintype "power_in"))
      (node (ref "ENVSENS_BME680") (pin "5") (pinfunction "SDO_5") (pintype "bidirectional"))
      (node (ref "ENVSENS_BME680") (pin "7") (pinfunction "GND_7") (pintype "power_in"))
      (node (ref "ENVSENS_C_1") (pin "2") (pinfunction "2_2") (pintype "passive"))
      (node (ref "ENVSENS_C_2") (pin "2") (pinfunction "2_2") (pintype "passive"))
      (node (ref "EPDC_C_2") (pin "2") (pinfunction "2_2") (pintype "passive"))
      (node (ref "EPDC_D_1") (pin "1") (pinfunction "K_1") (pintype "bidirectional"))
      (node (ref "EPDC_R_2") (pin "1") (pinfunction "1_1") (pintype "passive"))
      (node (ref "EPDH_C_1") (pin "1") (pinfunction "1_1") (pintype "passive"))
      (node (ref "EPDH_C_10") (pin "1") (pinfunction "1_1") (pintype "passive"))
      (node (ref "EPDH_C_2") (pin "1") (pinfunction "1_1") (pintype "passive"))
      (node (ref "EPDH_C_3") (pin "1") (pinfunction "1_1") (pintype "passive"))
      (node (ref "EPDH_C_4") (pin "1") (pinfunction "1_1") (pintype "passive"))
      (node (ref "EPDH_C_5") (pin "1") (pinfunction "1_1") (pintype "passive"))
      (node (ref "EPDH_C_6") (pin "1") (pinfunction "1_1") (pintype "passive"))
      (node (ref "EPDH_C_7") (pin "1") (pinfunction "1_1") (pintype "passive"))
      (node (ref "EPDH_C_8") (pin "1") (pinfunction "1_1") (pintype "passive"))
      (node (ref "EPDH_C_9") (pin "1") (pinfunction "1_1") (pintype "passive"))
      (node (ref "EPDH_HEADER") (pin "17") (pinfunction "17_17") (pintype "bidirectional"))
      (node (ref "EPDH_HEADER") (pin "8") (pinfunction "8_8") (pintype "bidirectional"))
      (node (ref "EPDH_HEADER") (pin "MP1") (pinfunction "MP1_MP1") (pintype "bidirectional"))
      (node (ref "EPDH_HEADER") (pin "MP2") (pinfunction "MP2_MP2") (pintype "bidirectional"))
      (node (ref "EPDTS_R") (pin "1") (pinfunction "1_1") (pintype "passive"))
      (node (ref "EPDTS_SJ") (pin "1") (pinfunction "1_1") (pintype "passive"))
      (node (ref "ESP32") (pin "1") (pinfunction "GND_1") (pintype "power_in"))
      (node (ref "ESP32") (pin "28") (pinfunction "GND_28") (pintype "power_in"))
      (node (ref "ESP32") (pin "29_1") (pinfunction "GND_29_1") (pintype "power_in"))
      (node (ref "ESP32") (pin "29_2") (pinfunction "GND_29_2") (pintype "power_in"))
      (node (ref "ESP32") (pin "29_3") (pinfunction "GND_29_3") (pintype "power_in"))
      (node (ref "ESP32") (pin "29_4") (pinfunction "GND_29_4") (pintype "power_in"))
      (node (ref "ESP32") (pin "29_5") (pinfunction "GND_29_5") (pintype "power_in"))
      (node (ref "ESP32") (pin "29_6") (pinfunction "GND_29_6") (pintype "power_in"))
      (node (ref "ESP32") (pin "29_7") (pinfunction "GND_29_7") (pintype "power_in"))
      (node (ref "ESP32") (pin "29_8") (pinfunction "GND_29_8") (pintype "power_in"))
      (node (ref "ESP32") (pin "29_9") (pinfunction "GND_29_9") (pintype "power_in"))
      (node (ref "FLASH_NOR") (pin "4") (pinfunction "GND_4") (pintype "power_in"))
      (node (ref "FLASH_NOR") (pin "9") (pinfunction "EXP_9") (pintype "passive"))
      (node (ref "LPBCC_C_BAT_1") (pin "2") (pinfunction "2_2") (pintype "passive"))
      (node (ref "LPBCC_C_BAT_2") (pin "2") (pinfunction "2_2") (pintype "passive"))
      (node (ref "LPBCC_MCP73831") (pin "2") (pinfunction "VSS_2") (pintype "power_in"))
      (node (ref "LPBCC_R_BAT_2") (pin "1") (pinfunction "1_1") (pintype "passive"))
      (node (ref "QWIIC") (pin "1") (pinfunction "1_1") (pintype "power_in"))
      (node (ref "RTC_C") (pin "2") (pinfunction "2_2") (pintype "passive"))
      (node (ref "RTC_COUNTER") (pin "13") (pinfunction "GND_13") (pintype "power_in"))
      (node (ref "RTC_C_SUPERCAP") (pin "2") (pinfunction "2_2") (pintype "passive"))
      (node (ref "SDC_C") (pin "2") (pinfunction "2_2") (pintype "passive"))
      (node (ref "SDC_SDC") (pin "G1") (pinfunction "GND_1_G1") (pintype "bidirectional"))
      (node (ref "SDC_SDC") (pin "G2") (pinfunction "GND_2_G2") (pintype "bidirectional"))
      (node (ref "SDC_SDC") (pin "G3") (pinfunction "GND_3_G3") (pintype "bidirectional"))
      (node (ref "SDC_SDC") (pin "G4") (pinfunction "GND_4_G4") (pintype "bidirectional"))
      (node (ref "SDC_SDC") (pin "P6") (pinfunction "VSS_P6") (pintype "bidirectional"))
      (node (ref "SPIESD_D_1") (pin "1") (pinfunction "1_1") (pintype "passive"))
      (node (ref "SPIESD_D_2") (pin "1") (pinfunction "1_1") (pintype "passive"))
      (node (ref "SPIESD_D_3") (pin "1") (pinfunction "1_1") (pintype "passive"))
      (node (ref "SPIESD_D_4") (pin "1") (pinfunction "1_1") (pintype "passive"))
      (node (ref "SPIESD_D_5") (pin "1") (pinfunction "1_1") (pintype "passive"))
      (node (ref "SPIESD_D_6") (pin "1") (pinfunction "1_1") (pintype "passive"))
      (node (ref "TP4") (pin "TP") (pinfunction "TP_TP") (pintype "input"))
      (node (ref "TP5") (pin "TP") (pinfunction "TP_TP") (pintype "input"))
      (node (ref "USBC_C_USB_1") (pin "2") (pinfunction "2_2") (pintype "passive"))
      (node (ref "USBC_C_USB_2") (pin "2") (pinfunction "2_2") (pintype "passive"))
      (node (ref "USBC_R_USB_1") (pin "1") (pinfunction "1_1") (pintype "passive"))
      (node (ref "USBC_R_USB_2") (pin "2") (pinfunction "2_2") (pintype "passive"))
      (node (ref "USBC_USB") (pin "A1") (pinfunction "A1_A1") (pintype "bidirectional"))
      (node (ref "USBC_USB") (pin "A12") (pinfunction "A12_A12") (pintype "bidirectional"))
      (node (ref "USBC_USB") (pin "B1") (pinfunction "B1_B1") (pintype "bidirectional"))
      (node (ref "USBC_USB") (pin "B12") (pinfunction "B12_B12") (pintype "bidirectional"))
      (node (ref "USBC_USB") (pin "MP1") (pinfunction "MP1_MP1") (pintype "bidirectional"))
      (node (ref "USBC_USB") (pin "MP2") (pinfunction "MP2_MP2") (pintype "bidirectional"))
      (node (ref "USBC_USB") (pin "MP3") (pinfunction "MP3_MP3") (pintype "bidirectional"))
      (node (ref "USBC_USB") (pin "MP4") (pinfunction "MP4_MP4") (pintype "bidirectional"))
      (node (ref "USBC_USBLC6-2SC6Y") (pin "2") (pinfunction "GND_2") (pintype "bidirectional"))
      (node (ref "VOLREG_C_BAT_1") (pin "2") (pinfunction "2_2") (pintype "passive"))
      (node (ref "VOLREG_C_BAT_2") (pin "2") (pinfunction "2_2") (pintype "passive"))
      (node (ref "VOLREG_C_SUPER") (pin "-") (pinfunction "-_-") (pintype "passive"))
      (node (ref "VOLREG_R") (pin "1") (pinfunction "1_1") (pintype "passive"))
      (node (ref "VOLREG_XC6220A331MR-G") (pin "2") (pinfunction "VSS_2") (pintype "bidirectional"))
      (node (ref "VOLSPV_BD5229G-TR") (pin "3") (pinfunction "GND_3") (pintype "bidirectional"))
      (node (ref "VOLSPV_BOOT_BUTTON") (pin "1") (pinfunction "1_1") (pintype "passive"))
      (node (ref "VOLSPV_BOOT_BUTTON") (pin "2") (pinfunction "2_2") (pintype "passive"))
      (node (ref "VOLSPV_CHANGE_BUTTON") (pin "1") (pinfunction "1_1") (pintype "passive"))
      (node (ref "VOLSPV_CHANGE_BUTTON") (pin "2") (pinfunction "2_2") (pintype "passive"))
      (node (ref "VOLSPV_C_5") (pin "2") (pinfunction "2_2") (pintype "passive"))
      (node (ref "VOLSPV_C_6") (pin "2") (pinfunction "2_2") (pintype "passive"))
      (node (ref "VOLSPV_C_7") (pin "2") (pinfunction "2_2") (pintype "passive"))
      (node (ref "VOLSPV_C_DELAY") (pin "2") (pinfunction "2_2") (pintype "passive"))
      (node (ref "VOLSPV_RESET_BUTTON") (pin "1") (pinfunction "1_1") (pintype "passive"))
      (node (ref "VOLSPV_RESET_BUTTON") (pin "2") (pinfunction "2_2") (pintype "passive"))
    )
    (net (code "14") (name "I2C_PW") (class "Default")
      (node (ref "ENVSENS_BME680") (pin "6") (pinfunction "VDDIO_6") (pintype "power_in"))
      (node (ref "ENVSENS_C_1") (pin "1") (pinfunction "1_1") (pintype "passive"))
      (node (ref "ENVSENS_C_2") (pin "1") (pinfunction "1_1") (pintype "passive"))
      (node (ref "ENVSENS_R_PINH_1") (pin "2") (pinfunction "2_2") (pintype "passive"))
      (node (ref "ENVSENS_R_PINH_2") (pin "2") (pinfunction "2_2") (pintype "passive"))
      (node (ref "ESP32") (pin "17") (pinfunction "IO19_17") (pintype "bidirectional"))
    )
    (net (code "15") (name "INT_RTC") (class "Default")
      (node (ref "ESP32") (pin "8") (pinfunction "IO0_8") (pintype "bidirectional"))
      (node (ref "RTC_COUNTER") (pin "3") (pinfunction "SQW/~{INT}_3") (pintype "output"))
      (node (ref "RTC_R_PINH1_1") (pin "1") (pinfunction "1_1") (pintype "passive"))
      (node (ref "TP15") (pin "TP") (pinfunction "TP_TP") (pintype "input"))
    )
    (net (code "16") (name "IO{slash}BOOT") (class "Default")
      (node (ref "ESP32") (pin "15") (pinfunction "IO9_15") (pintype "bidirectional"))
      (node (ref "VOLSPV_BOOT_BUTTON") (pin "3") (pinfunction "3_3") (pintype "passive"))
      (node (ref "VOLSPV_BOOT_BUTTON") (pin "4") (pinfunction "4_4") (pintype "passive"))
      (node (ref "VOLSPV_C_6") (pin "1") (pinfunction "1_1") (pintype "passive"))
      (node (ref "VOLSPV_R_BOOT") (pin "1") (pinfunction "1_1") (pintype "passive"))
    )
    (net (code "17") (name "IO{slash}CHANGE") (class "Default")
      (node (ref "ESP32") (pin "23") (pinfunction "IO15_23") (pintype "bidirectional"))
      (node (ref "VOLSPV_CHANGE_BUTTON") (pin "3") (pinfunction "3_3") (pintype "passive"))
      (node (ref "VOLSPV_CHANGE_BUTTON") (pin "4") (pinfunction "4_4") (pintype "passive"))
      (node (ref "VOLSPV_C_7") (pin "1") (pinfunction "1_1") (pintype "passive"))
      (node (ref "VOLSPV_R_CHANGE") (pin "1") (pinfunction "1_1") (pintype "passive"))
    )
    (net (code "18") (name "MISO") (class "Default")
      (node (ref "ESP32") (pin "27") (pinfunction "IO2_27") (pintype "bidirectional"))
      (node (ref "FLASH_NOR") (pin "2") (pinfunction "DO(IO1)_2") (pintype "bidirectional"))
      (node (ref "SDC_SDC") (pin "P7") (pinfunction "DAT0_P7") (pintype "bidirectional"))
      (node (ref "SPIESD_D_1") (pin "2") (pinfunction "2_2") (pintype "passive"))
      (node (ref "SPIESD_R_1") (pin "1") (pinfunction "1_1") (pintype "passive"))
      (node (ref "TP6") (pin "TP") (pinfunction "TP_TP") (pintype "input"))
    )
    (net (code "19") (name "MOSI") (class "Default")
      (node (ref "EPDH_HEADER") (pin "14") (pinfunction "14_14") (pintype "bidirectional"))
      (node (ref "ESP32") (pin "7") (pinfunction "IO7_7") (pintype "bidirectional"))
      (node (ref "FLASH_NOR") (pin "5") (pinfunction "DI(IO0)_5") (pintype "bidirectional"))
      (node (ref "SDC_SDC") (pin "P3") (pinfunction "CMD_P3") (pintype "bidirectional"))
      (node (ref "SPIESD_D_2") (pin "2") (pinfunction "2_2") (pintype "passive"))
      (node (ref "SPIESD_R_2") (pin "1") (pinfunction "1_1") (pintype "passive"))
      (node (ref "TP7") (pin "TP") (pinfunction "TP_TP") (pintype "input"))
    )
    (net (code "20") (name "Net-(ENVSENS_BME680-CSB)") (class "Default")
      (node (ref "ENVSENS_BME680") (pin "2") (pinfunction "CSB_2") (pintype "input"))
      (node (ref "ENVSENS_BME680") (pin "8") (pinfunction "VDD_8") (pintype "power_in"))
    )
    (net (code "21") (name "Net-(EPDC_D_1-A)") (class "Default")
      (node (ref "EPDC_C_1") (pin "1") (pinfunction "1_1") (pintype "passive"))
      (node (ref "EPDC_D_1") (pin "2") (pinfunction "A_2") (pintype "bidirectional"))
      (node (ref "EPDC_D_2") (pin "1") (pinfunction "K_1") (pintype "bidirectional"))
    )
    (net (code "22") (name "Net-(EPDH_C_1-Pad2)") (class "Default")
      (node (ref "EPDH_C_1") (pin "2") (pinfunction "2_2") (pintype "passive"))
      (node (ref "EPDH_HEADER") (pin "4") (pinfunction "4_4") (pintype "bidirectional"))
    )
    (net (code "23") (name "Net-(EPDH_C_2-Pad2)") (class "Default")
      (node (ref "EPDH_C_2") (pin "2") (pinfunction "2_2") (pintype "passive"))
      (node (ref "EPDH_HEADER") (pin "5") (pinfunction "5_5") (pintype "bidirectional"))
    )
    (net (code "24") (name "Net-(EPDH_C_4-Pad2)") (class "Default")
      (node (ref "EPDH_C_4") (pin "2") (pinfunction "2_2") (pintype "passive"))
      (node (ref "EPDH_HEADER") (pin "18") (pinfunction "18_18") (pintype "bidirectional"))
    )
    (net (code "25") (name "Net-(EPDH_C_5-Pad2)") (class "Default")
      (node (ref "EPDH_C_5") (pin "2") (pinfunction "2_2") (pintype "passive"))
      (node (ref "EPDH_HEADER") (pin "19") (pinfunction "19_19") (pintype "bidirectional"))
    )
    (net (code "26") (name "Net-(EPDH_C_6-Pad2)") (class "Default")
      (node (ref "EPDH_C_6") (pin "2") (pinfunction "2_2") (pintype "passive"))
      (node (ref "EPDH_HEADER") (pin "20") (pinfunction "20_20") (pintype "bidirectional"))
    )
    (net (code "27") (name "Net-(EPDH_C_8-Pad2)") (class "Default")
      (node (ref "EPDH_C_8") (pin "2") (pinfunction "2_2") (pintype "passive"))
      (node (ref "EPDH_HEADER") (pin "22") (pinfunction "22_22") (pintype "bidirectional"))
    )
    (net (code "28") (name "Net-(EPDH_C_10-Pad2)") (class "Default")
      (node (ref "EPDH_C_10") (pin "2") (pinfunction "2_2") (pintype "passive"))
      (node (ref "EPDH_HEADER") (pin "24") (pinfunction "24_24") (pintype "bidirectional"))
    )
    (net (code "29") (name "Net-(ESP32-IO8)") (class "Default")
      (node (ref "ESP32") (pin "10") (pinfunction "IO8_10") (pintype "bidirectional"))
      (node (ref "ESP_R") (pin "1") (pinfunction "1_1") (pintype "passive"))
    )
    (net (code "30") (name "Net-(LPBCC_CHG_LED-PadC)") (class "Default")
      (node (ref "LPBCC_CHG_LED") (pin "C") (pinfunction "C_C") (pintype "passive"))
      (node (ref "LPBCC_R_BAT_1") (pin "1") (pinfunction "1_1") (pintype "passive"))
    )
    (net (code "31") (name "Net-(LPBCC_MCP73831-PROG)") (class "Default")
      (node (ref "LPBCC_MCP73831") (pin "5") (pinfunction "PROG_5") (pintype "input"))
      (node (ref "LPBCC_R_BAT_2") (pin "2") (pinfunction "2_2") (pintype "passive"))
    )
    (net (code "32") (name "Net-(LPBCC_MCP73831-STAT)") (class "Default")
      (node (ref "LPBCC_MCP73831") (pin "1") (pinfunction "STAT_1") (pintype "output"))
      (node (ref "LPBCC_R_BAT_1") (pin "2") (pinfunction "2_2") (pintype "passive"))
    )
    (net (code "33") (name "Net-(RTC_D-CATHODE)") (class "Default")
      (node (ref "RTC_D") (pin "1") (pinfunction "CATHODE_1") (pintype "bidirectional"))
      (node (ref "RTC_R_CAPACITOR") (pin "1") (pinfunction "1_1") (pintype "passive"))
    )
    (net (code "34") (name "Net-(USBC_R_USB_1-Pad2)") (class "Default")
      (node (ref "USBC_R_USB_1") (pin "2") (pinfunction "2_2") (pintype "passive"))
      (node (ref "USBC_USB") (pin "A5") (pinfunction "A5_A5") (pintype "bidirectional"))
    )
    (net (code "35") (name "Net-(USBC_R_USB_2-Pad1)") (class "Default")
      (node (ref "USBC_R_USB_2") (pin "1") (pinfunction "1_1") (pintype "passive"))
      (node (ref "USBC_USB") (pin "B5") (pinfunction "B5_B5") (pintype "bidirectional"))
    )
    (net (code "36") (name "Net-(VOLREG_D-CATHODE)") (class "Default")
      (node (ref "VOLREG_C_BAT_1") (pin "1") (pinfunction "1_1") (pintype "passive"))
      (node (ref "VOLREG_D") (pin "1") (pinfunction "CATHODE_1") (pintype "bidirectional"))
      (node (ref "VOLREG_MOSFET") (pin "2") (pinfunction "S_2") (pintype "bidirectional"))
      (node (ref "VOLREG_XC6220A331MR-G") (pin "1") (pinfunction "VIN_1") (pintype "bidirectional"))
      (node (ref "VOLREG_XC6220A331MR-G") (pin "3") (pinfunction "CE_3") (pintype "bidirectional"))
    )
    (net (code "37") (name "Net-(VOLSPV_BD5229G-TR-CT)") (class "Default")
      (node (ref "VOLSPV_BD5229G-TR") (pin "5") (pinfunction "CT_5") (pintype "bidirectional"))
      (node (ref "VOLSPV_C_DELAY") (pin "1") (pinfunction "1_1") (pintype "passive"))
    )
    (net (code "38") (name "PREVGH") (class "Default")
      (node (ref "EPDC_D_3") (pin "1") (pinfunction "K_1") (pintype "bidirectional"))
      (node (ref "EPDH_C_7") (pin "2") (pinfunction "2_2") (pintype "passive"))
      (node (ref "EPDH_HEADER") (pin "21") (pinfunction "21_21") (pintype "bidirectional"))
    )
    (net (code "39") (name "PREVGL") (class "Default")
      (node (ref "EPDC_D_2") (pin "2") (pinfunction "A_2") (pintype "bidirectional"))
      (node (ref "EPDH_C_9") (pin "2") (pinfunction "2_2") (pintype "passive"))
      (node (ref "EPDH_HEADER") (pin "23") (pinfunction "23_23") (pintype "bidirectional"))
    )
    (net (code "40") (name "RESE") (class "Default")
      (node (ref "EPDC_Q") (pin "2") (pinfunction "S_2") (pintype "bidirectional"))
      (node (ref "EPDC_R_1") (pin "2") (pinfunction "2_2") (pintype "passive"))
      (node (ref "EPDH_HEADER") (pin "3") (pinfunction "3_3") (pintype "bidirectional"))
    )
    (net (code "41") (name "RESE'") (class "Default")
      (node (ref "EPDC_R_1") (pin "1") (pinfunction "1_1") (pintype "passive"))
      (node (ref "EPDTS_R") (pin "2") (pinfunction "2_2") (pintype "passive"))
      (node (ref "EPDTS_SJ") (pin "2") (pinfunction "2_2") (pintype "passive"))
    )
    (net (code "42") (name "RESET") (class "Default")
      (node (ref "ESP32") (pin "3") (pinfunction "EN_3") (pintype "input"))
      (node (ref "VOLSPV_BD5229G-TR") (pin "1") (pinfunction "VOUT_1") (pintype "bidirectional"))
      (node (ref "VOLSPV_C_5") (pin "1") (pinfunction "1_1") (pintype "passive"))
      (node (ref "VOLSPV_RESET_BUTTON") (pin "3") (pinfunction "3_3") (pintype "passive"))
      (node (ref "VOLSPV_RESET_BUTTON") (pin "4") (pinfunction "4_4") (pintype "passive"))
      (node (ref "VOLSPV_R_RESET") (pin "1") (pinfunction "1_1") (pintype "passive"))
    )
    (net (code "43") (name "RTC_RST") (class "Default")
      (node (ref "ESP32") (pin "16") (pinfunction "IO18_16") (pintype "bidirectional"))
      (node (ref "RTC_COUNTER") (pin "4") (pinfunction "~{RST}_4") (pintype "input"))
    )
    (net (code "44") (name "RX") (class "Default")
      (node (ref "ESP32") (pin "24") (pinfunction "RXD0/GPIO17_24") (pintype "bidirectional"))
      (node (ref "TP2") (pin "TP") (pinfunction "TP_TP") (pintype "input"))
    )
    (net (code "45") (name "SCK") (class "Default")
      (node (ref "EPDH_HEADER") (pin "13") (pinfunction "13_13") (pintype "bidirectional"))
      (node (ref "ESP32") (pin "6") (pinfunction "IO6_6") (pintype "bidirectional"))
      (node (ref "FLASH_NOR") (pin "6") (pinfunction "CLK_6") (pintype "input"))
      (node (ref "SDC_SDC") (pin "P5") (pinfunction "CLK_P5") (pintype "bidirectional"))
      (node (ref "SPIESD_D_3") (pin "2") (pinfunction "2_2") (pintype "passive"))
      (node (ref "SPIESD_R_3") (pin "1") (pinfunction "1_1") (pintype "passive"))
      (node (ref "TP8") (pin "TP") (pinfunction "TP_TP") (pintype "input"))
    )
    (net (code "46") (name "SCL") (class "Default")
      (node (ref "BCL_MAX17048G+T10") (pin "7") (pinfunction "SCL_7") (pintype "input"))
      (node (ref "ENVSENS_BME680") (pin "4") (pinfunction "SCK_4") (pintype "input"))
      (node (ref "ENVSENS_R_PINH_1") (pin "1") (pinfunction "1_1") (pintype "passive"))
      (node (ref "ESP32") (pin "20") (pinfunction "IO22_20") (pintype "bidirectional"))
      (node (ref "QWIIC") (pin "4") (pinfunction "4_4") (pintype "passive"))
      (node (ref "RTC_COUNTER") (pin "16") (pinfunction "SCL_16") (pintype "input"))
    )
    (net (code "47") (name "SDA") (class "Default")
      (node (ref "BCL_MAX17048G+T10") (pin "8") (pinfunction "SDA_8") (pintype "bidirectional"))
      (node (ref "ENVSENS_BME680") (pin "3") (pinfunction "SDI_3") (pintype "bidirectional"))
      (node (ref "ENVSENS_R_PINH_2") (pin "1") (pinfunction "1_1") (pintype "passive"))
      (node (ref "ESP32") (pin "19") (pinfunction "IO21_19") (pintype "bidirectional"))
      (node (ref "QWIIC") (pin "3") (pinfunction "3_3") (pintype "passive"))
      (node (ref "RTC_COUNTER") (pin "15") (pinfunction "SDA_15") (pintype "bidirectional"))
    )
    (net (code "48") (name "SRC") (class "Default")
      (node (ref "EPDC_C_1") (pin "2") (pinfunction "2_2") (pintype "passive"))
      (node (ref "EPDC_D_3") (pin "2") (pinfunction "A_2") (pintype "bidirectional"))
      (node (ref "EPDC_L") (pin "1") (pinfunction "1_1") (pintype "passive"))
      (node (ref "EPDC_Q") (pin "3") (pinfunction "D_3") (pintype "bidirectional"))
    )
    (net (code "49") (name "SS_SD") (class "Default")
      (node (ref "ESP32") (pin "4") (pinfunction "IO4_4") (pintype "bidirectional"))
      (node (ref "SDC_SDC") (pin "P2") (pinfunction "CD/DAT3_P2") (pintype "bidirectional"))
      (node (ref "SPIESD_D_6") (pin "2") (pinfunction "2_2") (pintype "passive"))
      (node (ref "SPIESD_R_6") (pin "1") (pinfunction "1_1") (pintype "passive"))
    )
    (net (code "50") (name "TX") (class "Default")
      (node (ref "ESP32") (pin "25") (pinfunction "TXD0/GPIO16_25") (pintype "bidirectional"))
      (node (ref "TP1") (pin "TP") (pinfunction "TP_TP") (pintype "input"))
    )
    (net (code "51") (name "USB_D+") (class "Default")
      (node (ref "ESP32") (pin "14") (pinfunction "IO13_14") (pintype "bidirectional"))
      (node (ref "USBC_USBLC6-2SC6Y") (pin "1") (pinfunction "I/O1_1_1") (pintype "bidirectional"))
    )
    (net (code "52") (name "USB_D-") (class "Default")
      (node (ref "ESP32") (pin "13") (pinfunction "IO12_13") (pintype "bidirectional"))
      (node (ref "USBC_USBLC6-2SC6Y") (pin "3") (pinfunction "I/O2_1_3") (pintype "bidirectional"))
    )
    (net (code "53") (name "VBAT") (class "Default")
      (node (ref "BCL_MAX17048G+T10") (pin "2") (pinfunction "CELL_2") (pintype "power_in"))
      (node (ref "BCL_MAX17048G+T10") (pin "3") (pinfunction "VDD_3") (pintype "power_in"))
      (node (ref "LPBCC_C_BAT_2") (pin "1") (pinfunction "1_1") (pintype "passive"))
      (node (ref "LPBCC_MCP73831") (pin "3") (pinfunction "VBAT_3") (pintype "power_in"))
      (node (ref "TP3") (pin "TP") (pinfunction "TP_TP") (pintype "input"))
      (node (ref "VOLREG_MOSFET") (pin "3") (pinfunction "D_3") (pintype "bidirectional"))
    )
    (net (code "54") (name "VBUS") (class "Default")
      (node (ref "LPBCC_CHG_LED") (pin "A") (pinfunction "A_A") (pintype "passive"))
      (node (ref "LPBCC_C_BAT_1") (pin "1") (pinfunction "1_1") (pintype "passive"))
      (node (ref "LPBCC_MCP73831") (pin "4") (pinfunction "VIN_4") (pintype "power_in"))
      (node (ref "TP14") (pin "TP") (pinfunction "TP_TP") (pintype "input"))
      (node (ref "USBC_C_USB_1") (pin "1") (pinfunction "1_1") (pintype "passive"))
      (node (ref "USBC_C_USB_2") (pin "1") (pinfunction "1_1") (pintype "passive"))
      (node (ref "USBC_USBLC6-2SC6Y") (pin "5") (pinfunction "VBUS_5") (pintype "bidirectional"))
      (node (ref "USBC_VARISTOR") (pin "2") (pinfunction "2_2") (pintype "passive"))
      (node (ref "VOLREG_D") (pin "2") (pinfunction "ANODE_2") (pintype "bidirectional"))
      (node (ref "VOLREG_MOSFET") (pin "1") (pinfunction "G_1") (pintype "bidirectional"))
      (node (ref "VOLREG_R") (pin "2") (pinfunction "2_2") (pintype "passive"))
    )
    (net (code "55") (name "VRTC") (class "Default")
      (node (ref "RTC_C") (pin "1") (pinfunction "1_1") (pintype "passive"))
      (node (ref "RTC_COUNTER") (pin "14") (pinfunction "VBAT_14") (pintype "power_in"))
      (node (ref "RTC_C_SUPERCAP") (pin "1") (pinfunction "1_1") (pintype "passive"))
      (node (ref "RTC_R_CAPACITOR") (pin "2") (pinfunction "2_2") (pintype "passive"))
    )
    (net (code "56") (name "VUSB") (class "Default")
      (node (ref "USBC_USB") (pin "A4") (pinfunction "A4_A4") (pintype "bidirectional"))
      (node (ref "USBC_USB") (pin "A9") (pinfunction "A9_A9") (pintype "bidirectional"))
      (node (ref "USBC_USB") (pin "B4") (pinfunction "B4_B4") (pintype "bidirectional"))
      (node (ref "USBC_USB") (pin "B9") (pinfunction "B9_B9") (pintype "bidirectional"))
      (node (ref "USBC_VARISTOR") (pin "1") (pinfunction "1_1") (pintype "passive"))
    )
    (net (code "57") (name "unconnected-(BCL_MAX17048G+T10-~{ALERT}-Pad5)") (class "Default")
      (node (ref "BCL_MAX17048G+T10") (pin "5") (pinfunction "~{ALERT}_5") (pintype "output"))
    )
    (net (code "58") (name "unconnected-(EPDH_HEADER-Pad1)") (class "Default")
      (node (ref "EPDH_HEADER") (pin "1") (pinfunction "1_1") (pintype "bidirectional"))
    )
    (net (code "59") (name "unconnected-(EPDH_HEADER-Pad6)") (class "Default")
      (node (ref "EPDH_HEADER") (pin "6") (pinfunction "6_6") (pintype "bidirectional"))
    )
    (net (code "60") (name "unconnected-(EPDH_HEADER-Pad7)") (class "Default")
      (node (ref "EPDH_HEADER") (pin "7") (pinfunction "7_7") (pintype "bidirectional"))
    )
    (net (code "61") (name "unconnected-(ESP32-NC-Pad22)") (class "Default")
      (node (ref "ESP32") (pin "22") (pinfunction "NC_22") (pintype "no_connect"))
    )
    (net (code "62") (name "unconnected-(SDC_SDC-DAT1-PadP8)") (class "Default")
      (node (ref "SDC_SDC") (pin "P8") (pinfunction "DAT1_P8") (pintype "bidirectional"))
    )
    (net (code "63") (name "unconnected-(SDC_SDC-DAT2-PadP1)") (class "Default")
      (node (ref "SDC_SDC") (pin "P1") (pinfunction "DAT2_P1") (pintype "bidirectional"))
    )
    (net (code "64") (name "unconnected-(SDC_SDC-DETECTION_1-PadS1)") (class "Default")
      (node (ref "SDC_SDC") (pin "S1") (pinfunction "DETECTION_1_S1") (pintype "bidirectional"))
    )
    (net (code "65") (name "unconnected-(SDC_SDC-DETECTION_2-PadS2)") (class "Default")
      (node (ref "SDC_SDC") (pin "S2") (pinfunction "DETECTION_2_S2") (pintype "bidirectional"))
    )
    (net (code "66") (name "unconnected-(USBC_USB-PadA8)") (class "Default")
      (node (ref "USBC_USB") (pin "A8") (pinfunction "A8_A8") (pintype "bidirectional"))
    )
    (net (code "67") (name "unconnected-(USBC_USB-PadB8)") (class "Default")
      (node (ref "USBC_USB") (pin "B8") (pinfunction "B8_B8") (pintype "bidirectional"))
    )
    (net (code "68") (name "unconnected-(VOLREG_XC6220A331MR-G-NC-Pad4)") (class "Default")
      (node (ref "VOLREG_XC6220A331MR-G") (pin "4") (pinfunction "NC_4") (pintype "no_connect"))
    )
    (net (code "69") (name "unconnected-(VOLSPV_BD5229G-TR-NC-Pad4)") (class "Default")
      (node (ref "VOLSPV_BD5229G-TR") (pin "4") (pinfunction "NC_4") (pintype "no_connect"))
    )
  )
)
